# PLC-_-V3.net
KiCad netlist of a schematic drawn in Altium Designer
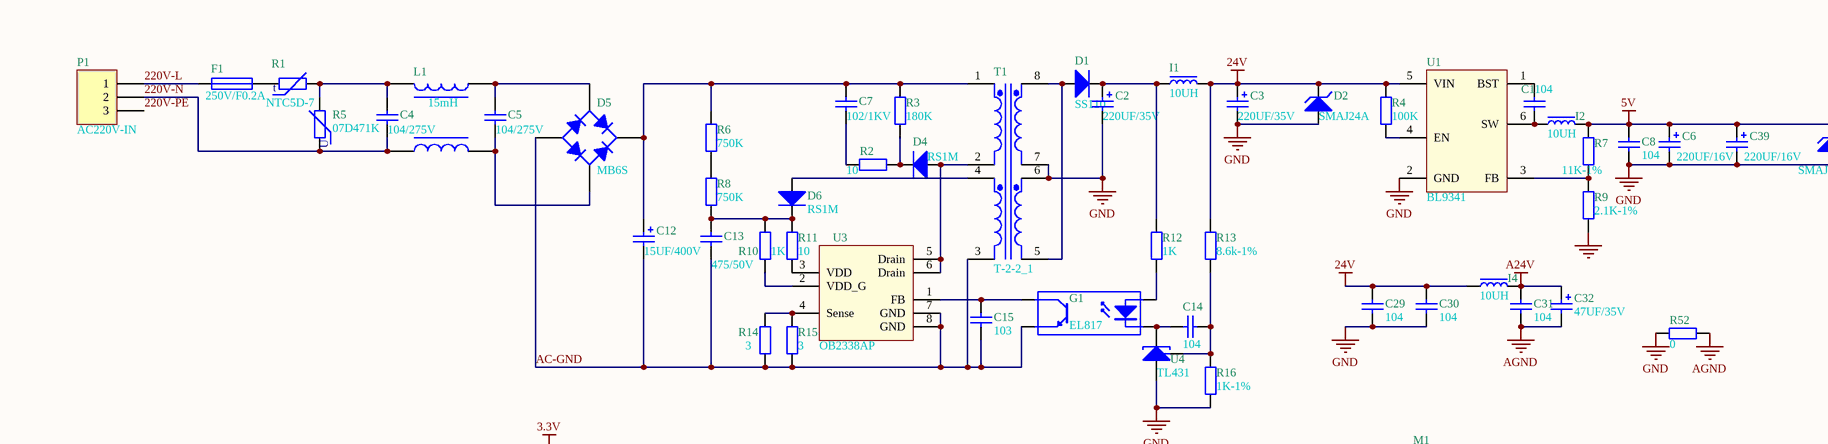
[diagram p0: PLC-无线通讯版-V3.SchDoc, top left]
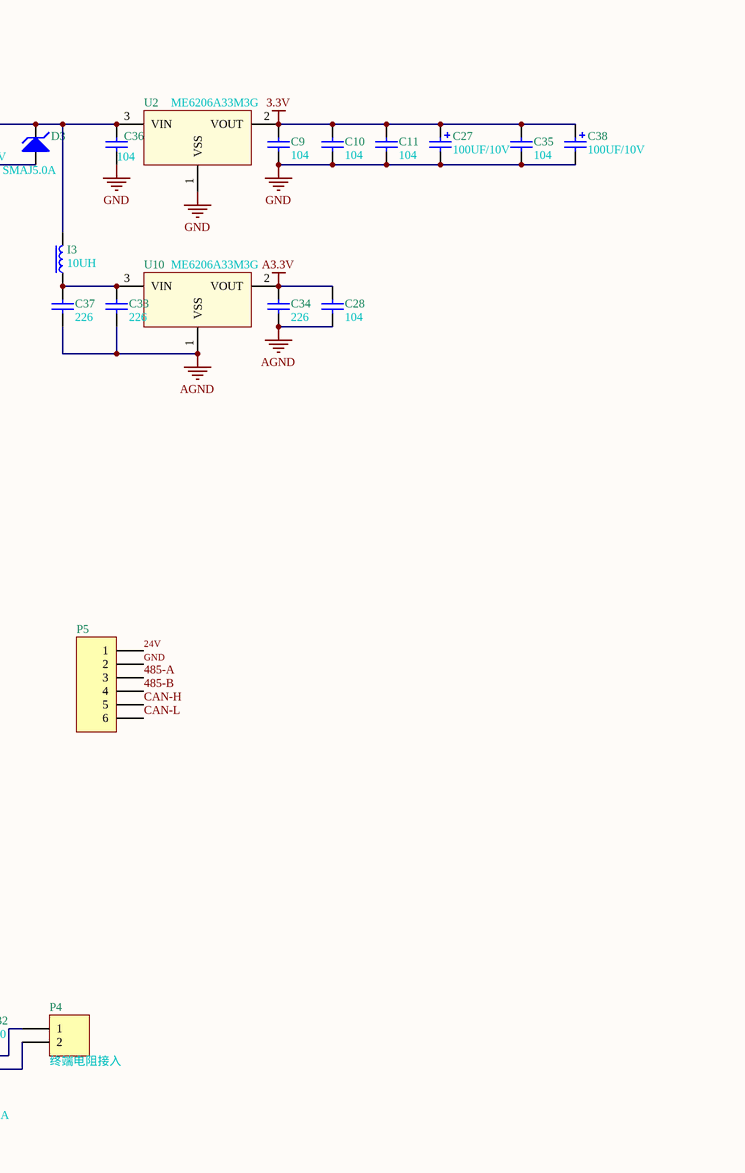
[diagram p1: PLC-无线通讯版-V3.SchDoc, top right]
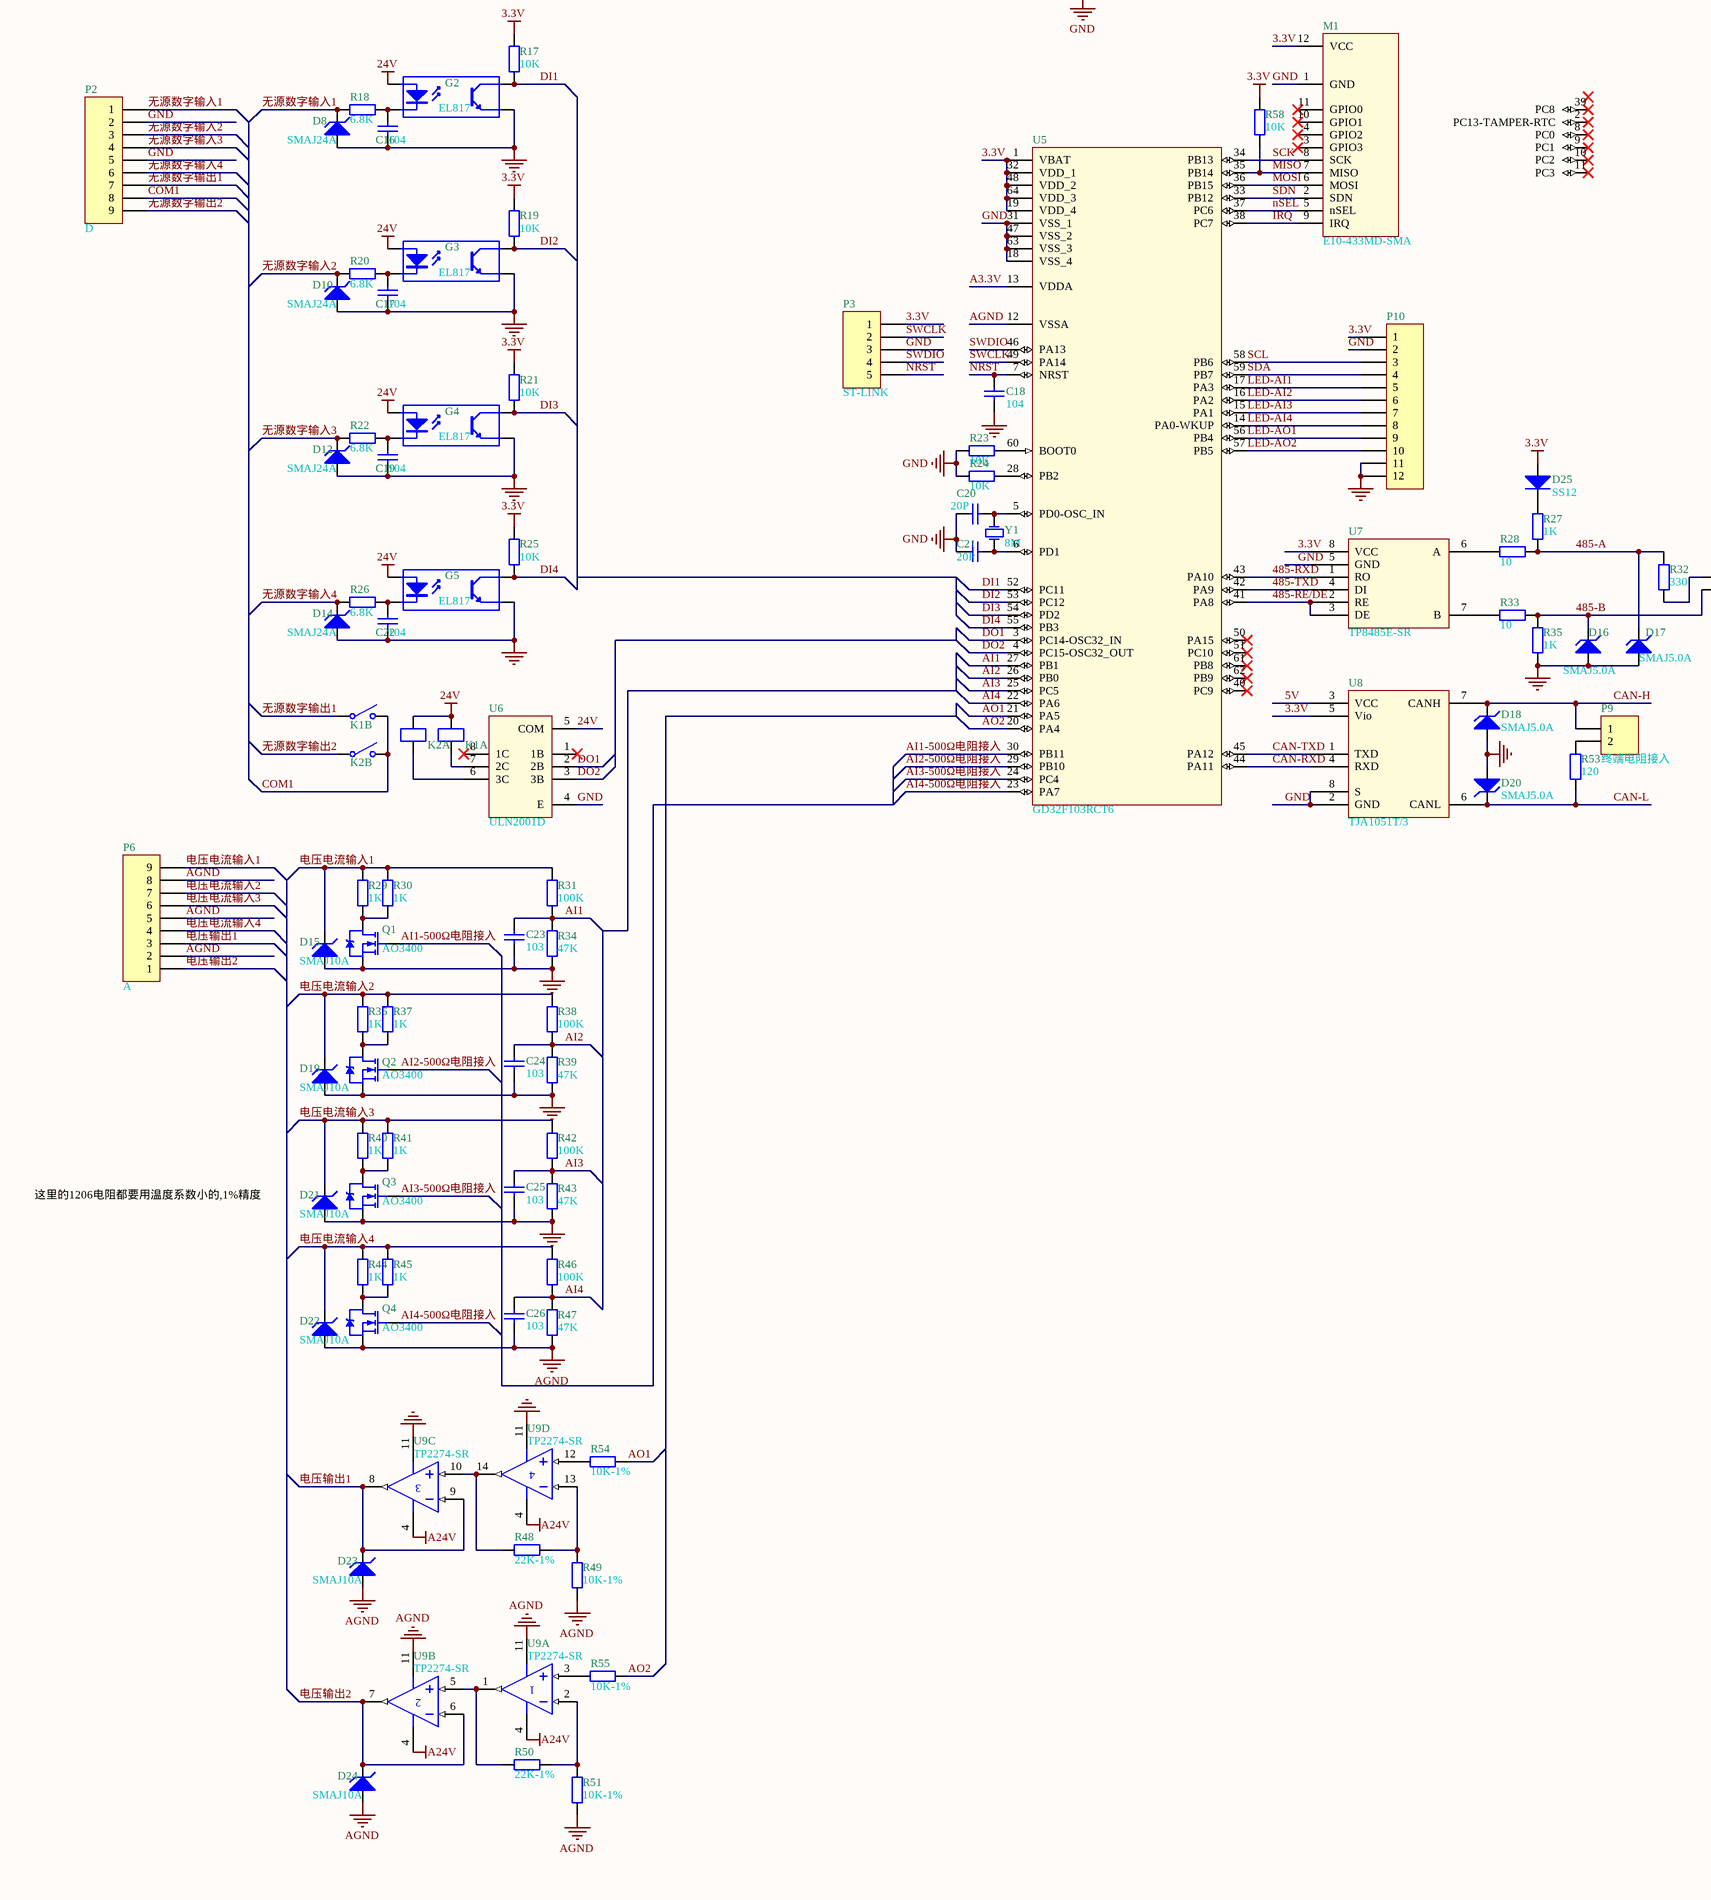
[diagram p2: PLC-无线通讯版-V3.SchDoc, bottom left]
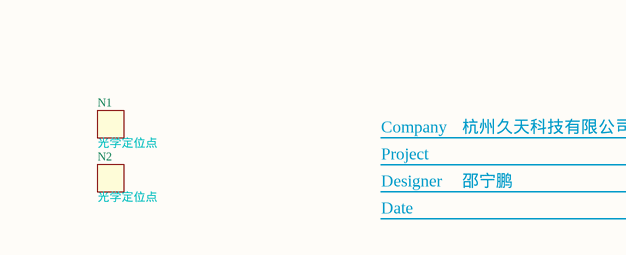
[diagram p3: PLC-无线通讯版-V3.SchDoc, bottom right]

(export (version "E")
  (design (tool "Eeschema 10.0.6"))
  (components
    (comp (ref "C1")
      (value "104")
      (footprint "C-0603")
      (description "Capacitor")
      (fields (field (name "PUBLISHER") "Altium Limited"))
      (libsource (lib "元件2.0") (part "Cap"))
    )
    (comp (ref "C2")
      (value "220UF/35V")
      (footprint "贴片固态电容8*10-M")
      (description "电解电容")
      (fields (field (name "PUBLISHER") "Altium Limited"))
      (libsource (lib "2电容-V1.0") (part "Cap Pol1"))
    )
    (comp (ref "C3")
      (value "220UF/35V")
      (footprint "贴片固态电容8*10-M")
      (description "电解电容")
      (fields (field (name "PUBLISHER") "Altium Limited"))
      (libsource (lib "2电容-V1.0") (part "Cap Pol1"))
    )
    (comp (ref "C4")
      (value "104/275V")
      (footprint "安规电容 脚距10")
      (description "Capacitor")
      (fields (field (name "PUBLISHER") "Altium Limited"))
      (libsource (lib "元件2.0") (part "Cap"))
    )
    (comp (ref "C5")
      (value "104/275V")
      (footprint "安规电容 脚距10")
      (description "Capacitor")
      (fields (field (name "PUBLISHER") "Altium Limited"))
      (libsource (lib "元件2.0") (part "Cap"))
    )
    (comp (ref "C6")
      (value "220UF/16V")
      (footprint "贴片固态电容6.3*7.7")
      (description "Polarized Capacitor (Radial)")
      (fields (field (name "PUBLISHER") "Altium Limited"))
      (libsource (lib "元件2.0") (part "Cap Pol1"))
    )
    (comp (ref "C7")
      (value "102/1KV")
      (footprint "C-1206-M")
      (description "0805")
      (fields (field (name "PUBLISHER") "Altium Limited"))
      (libsource (lib "2电容-V1.0") (part "Cap-0603"))
    )
    (comp (ref "C8")
      (value "104")
      (footprint "C-0603")
      (description "Capacitor")
      (fields (field (name "PUBLISHER") "Altium Limited"))
      (libsource (lib "元件2.0") (part "Cap"))
    )
    (comp (ref "C9")
      (value "104")
      (footprint "C-0603")
      (description "Capacitor")
      (fields (field (name "PUBLISHER") "Altium Limited"))
      (libsource (lib "元件2.0") (part "Cap"))
    )
    (comp (ref "C10")
      (value "104")
      (footprint "C-0603")
      (description "Capacitor")
      (fields (field (name "PUBLISHER") "Altium Limited"))
      (libsource (lib "元件2.0") (part "Cap"))
    )
    (comp (ref "C11")
      (value "104")
      (footprint "C-0603")
      (description "Capacitor")
      (fields (field (name "PUBLISHER") "Altium Limited"))
      (libsource (lib "元件2.0") (part "Cap"))
    )
    (comp (ref "C12")
      (value "15UF/400V")
      (footprint "电解电容10*20蓝色")
      (description "电解电容")
      (fields (field (name "PUBLISHER") "Altium Limited"))
      (libsource (lib "2电容-V1.0") (part "Cap Pol1"))
    )
    (comp (ref "C13")
      (value "475/50V")
      (footprint "C-1206-M")
      (description "Capacitor")
      (fields (field (name "PUBLISHER") "Altium Limited"))
      (libsource (lib "元件2.0") (part "Cap"))
    )
    (comp (ref "C14")
      (value "104")
      (footprint "C-0603")
      (description "Capacitor")
      (fields (field (name "PUBLISHER") "Altium Limited"))
      (libsource (lib "元件2.0") (part "Cap"))
    )
    (comp (ref "C15")
      (value "103")
      (footprint "C-0603")
      (description "Capacitor")
      (fields (field (name "PUBLISHER") "Altium Limited"))
      (libsource (lib "元件2.0") (part "Cap"))
    )
    (comp (ref "C16")
      (value "104")
      (footprint "C-0603")
      (description "0805")
      (fields (field (name "PUBLISHER") "Altium Limited"))
      (libsource (lib "2电容-V1.0") (part "Cap-0603"))
    )
    (comp (ref "C17")
      (value "104")
      (footprint "C-0603")
      (description "0805")
      (fields (field (name "PUBLISHER") "Altium Limited"))
      (libsource (lib "2电容-V1.0") (part "Cap-0603"))
    )
    (comp (ref "C18")
      (value "104")
      (footprint "C-0603")
      (description "0805")
      (fields (field (name "PUBLISHER") "Altium Limited"))
      (libsource (lib "2电容-V1.0") (part "Cap-0603"))
    )
    (comp (ref "C19")
      (value "104")
      (footprint "C-0603")
      (description "0805")
      (fields (field (name "PUBLISHER") "Altium Limited"))
      (libsource (lib "2电容-V1.0") (part "Cap-0603"))
    )
    (comp (ref "C20")
      (value "20P")
      (footprint "C-0603")
      (description "0805")
      (fields (field (name "PUBLISHER") "Altium Limited"))
      (libsource (lib "2电容-V1.0") (part "Cap-0603"))
    )
    (comp (ref "C21")
      (value "20P")
      (footprint "C-0603")
      (description "0805")
      (fields (field (name "PUBLISHER") "Altium Limited"))
      (libsource (lib "2电容-V1.0") (part "Cap-0603"))
    )
    (comp (ref "C22")
      (value "104")
      (footprint "C-0603")
      (description "0805")
      (fields (field (name "PUBLISHER") "Altium Limited"))
      (libsource (lib "2电容-V1.0") (part "Cap-0603"))
    )
    (comp (ref "C23")
      (value "103")
      (footprint "C-0603")
      (description "0805")
      (fields (field (name "PUBLISHER") "Altium Limited"))
      (libsource (lib "2电容-V1.0") (part "Cap-0603"))
    )
    (comp (ref "C24")
      (value "103")
      (footprint "C-0603")
      (description "0805")
      (fields (field (name "PUBLISHER") "Altium Limited"))
      (libsource (lib "2电容-V1.0") (part "Cap-0603"))
    )
    (comp (ref "C25")
      (value "103")
      (footprint "C-0603")
      (description "0805")
      (fields (field (name "PUBLISHER") "Altium Limited"))
      (libsource (lib "2电容-V1.0") (part "Cap-0603"))
    )
    (comp (ref "C26")
      (value "103")
      (footprint "C-0603")
      (description "0805")
      (fields (field (name "PUBLISHER") "Altium Limited"))
      (libsource (lib "2电容-V1.0") (part "Cap-0603"))
    )
    (comp (ref "C27")
      (value "100UF/10V")
      (footprint "贴片固态电容5*5.3")
      (description "Polarized Capacitor (Radial)")
      (fields (field (name "PUBLISHER") "Altium Limited"))
      (libsource (lib "元件2.0") (part "Cap Pol1"))
    )
    (comp (ref "C28")
      (value "104")
      (footprint "C-0603")
      (description "Capacitor")
      (fields (field (name "PUBLISHER") "Altium Limited"))
      (libsource (lib "元件2.0") (part "Cap"))
    )
    (comp (ref "C29")
      (value "104")
      (footprint "C-0603")
      (description "Capacitor")
      (fields (field (name "PUBLISHER") "Altium Limited"))
      (libsource (lib "元件2.0") (part "Cap"))
    )
    (comp (ref "C30")
      (value "104")
      (footprint "C-0603")
      (description "Capacitor")
      (fields (field (name "PUBLISHER") "Altium Limited"))
      (libsource (lib "元件2.0") (part "Cap"))
    )
    (comp (ref "C31")
      (value "104")
      (footprint "C-0603")
      (description "Capacitor")
      (fields (field (name "PUBLISHER") "Altium Limited"))
      (libsource (lib "元件2.0") (part "Cap"))
    )
    (comp (ref "C32")
      (value "47UF/35V")
      (footprint "贴片固态电容6.3*5.3-M")
      (description "Polarized Capacitor (Radial)")
      (fields (field (name "PUBLISHER") "Altium Limited"))
      (libsource (lib "元件2.0") (part "Cap Pol1"))
    )
    (comp (ref "C33")
      (value "226")
      (footprint "C-0805")
      (description "Capacitor")
      (fields (field (name "PUBLISHER") "Altium Limited"))
      (libsource (lib "元件2.0") (part "Cap"))
    )
    (comp (ref "C34")
      (value "226")
      (footprint "C-0805")
      (description "Capacitor")
      (fields (field (name "PUBLISHER") "Altium Limited"))
      (libsource (lib "元件2.0") (part "Cap"))
    )
    (comp (ref "C35")
      (value "104")
      (footprint "C-0603")
      (description "Capacitor")
      (fields (field (name "PUBLISHER") "Altium Limited"))
      (libsource (lib "元件2.0") (part "Cap"))
    )
    (comp (ref "C36")
      (value "104")
      (footprint "C-0603")
      (description "Capacitor")
      (fields (field (name "PUBLISHER") "Altium Limited"))
      (libsource (lib "元件2.0") (part "Cap"))
    )
    (comp (ref "C37")
      (value "226")
      (footprint "C-0805")
      (description "Capacitor")
      (fields (field (name "PUBLISHER") "Altium Limited"))
      (libsource (lib "元件2.0") (part "Cap"))
    )
    (comp (ref "C38")
      (value "100UF/10V")
      (footprint "贴片固态电容5*5.3")
      (description "Polarized Capacitor (Radial)")
      (fields (field (name "PUBLISHER") "Altium Limited"))
      (libsource (lib "元件2.0") (part "Cap Pol1"))
    )
    (comp (ref "C39")
      (value "220UF/16V")
      (footprint "贴片固态电容6.3*7.7")
      (description "Polarized Capacitor (Radial)")
      (fields (field (name "PUBLISHER") "Altium Limited"))
      (libsource (lib "元件2.0") (part "Cap Pol1"))
    )
    (comp (ref "D1")
      (value "SS110")
      (footprint "SMA")
      (description "SMA")
      (libsource (lib "4二极管-V1.1") (part "SS14"))
    )
    (comp (ref "D2")
      (value "SMAJ24A")
      (footprint "SMA")
      (description "SMB")
      (libsource (lib "4二极管-V1.1") (part "TVS-1"))
    )
    (comp (ref "D3")
      (value "SMAJ5.0A")
      (footprint "SMA")
      (description "SMB")
      (libsource (lib "4二极管-V1.1") (part "TVS-1"))
    )
    (comp (ref "D4")
      (value "RS1M")
      (footprint "SMA")
      (description "SMA")
      (libsource (lib "4二极管-V1.1") (part "SS14"))
    )
    (comp (ref "D5")
      (value "MB6S")
      (footprint "SOIC-4-MBS")
      (description "整流桥堆 MB05S-MB10S")
      (libsource (lib "4二极管-V1.1") (part "MB6S"))
    )
    (comp (ref "D6")
      (value "RS1M")
      (footprint "SMA")
      (description "SMA")
      (libsource (lib "4二极管-V1.1") (part "SS14"))
    )
    (comp (ref "D8")
      (value "SMAJ24A")
      (footprint "SMA")
      (description "SMB")
      (libsource (lib "4二极管-V1.1") (part "TVS-1"))
    )
    (comp (ref "D10")
      (value "SMAJ24A")
      (footprint "SMA")
      (description "SMB")
      (libsource (lib "4二极管-V1.1") (part "TVS-1"))
    )
    (comp (ref "D12")
      (value "SMAJ24A")
      (footprint "SMA")
      (description "SMB")
      (libsource (lib "4二极管-V1.1") (part "TVS-1"))
    )
    (comp (ref "D14")
      (value "SMAJ24A")
      (footprint "SMA")
      (description "SMB")
      (libsource (lib "4二极管-V1.1") (part "TVS-1"))
    )
    (comp (ref "D15")
      (value "SMAJ10A")
      (footprint "SMA")
      (description "SMB")
      (libsource (lib "4二极管-V1.1") (part "TVS-1"))
    )
    (comp (ref "D16")
      (value "SMAJ5.0A")
      (footprint "SMA")
      (description "SMB")
      (libsource (lib "4二极管-V1.1") (part "TVS-1"))
    )
    (comp (ref "D17")
      (value "SMAJ5.0A")
      (footprint "SMA")
      (description "SMB")
      (libsource (lib "4二极管-V1.1") (part "TVS-1"))
    )
    (comp (ref "D18")
      (value "SMAJ5.0A")
      (footprint "SMA")
      (description "SMB")
      (libsource (lib "4二极管-V1.1") (part "TVS-1"))
    )
    (comp (ref "D19")
      (value "SMAJ10A")
      (footprint "SMA")
      (description "SMB")
      (libsource (lib "4二极管-V1.1") (part "TVS-1"))
    )
    (comp (ref "D20")
      (value "SMAJ5.0A")
      (footprint "SMA")
      (description "SMB")
      (libsource (lib "4二极管-V1.1") (part "TVS-1"))
    )
    (comp (ref "D21")
      (value "SMAJ10A")
      (footprint "SMA")
      (description "SMB")
      (libsource (lib "4二极管-V1.1") (part "TVS-1"))
    )
    (comp (ref "D22")
      (value "SMAJ10A")
      (footprint "SMA")
      (description "SMB")
      (libsource (lib "4二极管-V1.1") (part "TVS-1"))
    )
    (comp (ref "D23")
      (value "SMAJ10A")
      (footprint "SMA")
      (description "SMB")
      (libsource (lib "4二极管-V1.1") (part "TVS-1"))
    )
    (comp (ref "D24")
      (value "SMAJ10A")
      (footprint "SMA")
      (description "SMB")
      (libsource (lib "4二极管-V1.1") (part "TVS-1"))
    )
    (comp (ref "D25")
      (value "SS12")
      (footprint "SMA")
      (description "SMA")
      (libsource (lib "4二极管-V1.1") (part "SS14"))
    )
    (comp (ref "F1")
      (value "250V/F0.2A")
      (footprint "FUSE-3*10带引线")
      (description "Fuse")
      (fields (field (name "PUBLISHER") "Altium Limited"))
      (libsource (lib "11其他元件-V1.0") (part "Fuse 1"))
    )
    (comp (ref "G1")
      (value "EL817")
      (footprint "SOP-4-L")
      (fields (field (name "PUBLISHER") "Altium Limited"))
      (libsource (lib "4二极管-V1.1") (part "EL817"))
    )
    (comp (ref "G2")
      (value "EL817")
      (footprint "SOP-4-L")
      (fields (field (name "PUBLISHER") "Altium Limited"))
      (libsource (lib "4二极管-V1.1") (part "EL817"))
    )
    (comp (ref "G3")
      (value "EL817")
      (footprint "SOP-4-L")
      (fields (field (name "PUBLISHER") "Altium Limited"))
      (libsource (lib "4二极管-V1.1") (part "EL817"))
    )
    (comp (ref "G4")
      (value "EL817")
      (footprint "SOP-4-L")
      (fields (field (name "PUBLISHER") "Altium Limited"))
      (libsource (lib "4二极管-V1.1") (part "EL817"))
    )
    (comp (ref "G5")
      (value "EL817")
      (footprint "SOP-4-L")
      (fields (field (name "PUBLISHER") "Altium Limited"))
      (libsource (lib "4二极管-V1.1") (part "EL817"))
    )
    (comp (ref "I1") (value "10UH") (footprint "CD43-N") (libsource (lib "3电感-V1.0") (part "Inductance3")))
    (comp (ref "I2") (value "10UH") (footprint "CD54") (libsource (lib "3电感-V1.0") (part "Inductance3")))
    (comp (ref "I3") (value "10UH") (footprint "CD43-N") (libsource (lib "3电感-V1.0") (part "Inductance3")))
    (comp (ref "I4") (value "10UH") (footprint "CD43-N") (libsource (lib "3电感-V1.0") (part "Inductance3")))
    (comp (ref "K1")
      (value "HF49FD-D24-1H11")
      (footprint "HF49FD-D24-1H11")
      (libsource (lib "10继电器-V1.0") (part "HF49FD-D24-1H11"))
    )
    (comp (ref "K2")
      (value "HF49FD-D24-1H11")
      (footprint "HF49FD-D24-1H11")
      (libsource (lib "") (part "HF49FD-D24-1H11_1"))
    )
    (comp (ref "L1") (value "15mH") (footprint "UU9.8") (libsource (lib "3电感-V1.0") (part "共模电感UU9.8")))
    (comp (ref "M1")
      (value "E10-433MD-SMA")
      (footprint "E10-433MD-SMA")
      (libsource (lib "6电路模块-V1.0") (part "E10-433MD-SMA"))
    )
    (comp (ref "N1") (value "光学定位点") (footprint "MARK-1mm-3mm") (libsource (lib "11其他元件-V1.0") (part "无引脚")))
    (comp (ref "N2") (value "光学定位点") (footprint "MARK-1mm-3mm") (libsource (lib "11其他元件-V1.0") (part "无引脚")))
    (comp (ref "P1")
      (value "AC220V-IN")
      (footprint "KF2EDGVC-5.08-3P")
      (description "Header, 3-Pin")
      (fields (field (name "PUBLISHER") "Altium Limited"))
      (libsource (lib "5排针-V1.0") (part "Header 3"))
    )
    (comp (ref "P2")
      (value "D")
      (footprint "2EMGKG-5.08-9P")
      (description "Header, 9-Pin")
      (fields (field (name "PUBLISHER") "Altium Limited"))
      (libsource (lib "5排针-V1.0") (part "Header 9"))
    )
    (comp (ref "P3")
      (value "ST-LINK")
      (footprint "5P下载口")
      (description "Header, 5-Pin")
      (fields (field (name "PUBLISHER") "Altium Limited"))
      (libsource (lib "5排针-V1.0") (part "Header 5"))
    )
    (comp (ref "P4")
      (value "终端电阻接入")
      (footprint "HDR1X2")
      (description "Header, 2-Pin")
      (fields (field (name "PUBLISHER") "Altium Limited"))
      (libsource (lib "5排针-V1.0") (part "Header 2"))
    )
    (comp (ref "P5")
      (value "~")
      (footprint "2EMGKG-5.08-6P")
      (description "Header, 6-Pin")
      (fields (field (name "PUBLISHER") "Altium Limited"))
      (libsource (lib "5排针-V1.0") (part "Header 6"))
    )
    (comp (ref "P6")
      (value "A")
      (footprint "2EMGKG-5.08-9P")
      (description "Header, 9-Pin")
      (fields (field (name "PUBLISHER") "Altium Limited"))
      (libsource (lib "") (part "Header 9_1"))
    )
    (comp (ref "P9")
      (value "终端电阻接入")
      (footprint "HDR1X2")
      (description "Header, 2-Pin")
      (fields (field (name "PUBLISHER") "Altium Limited"))
      (libsource (lib "5排针-V1.0") (part "Header 2"))
    )
    (comp (ref "P10")
      (value "~")
      (footprint "FPC-1.0MM立贴错位_10P")
      (description "Header, 12-Pin")
      (fields (field (name "PUBLISHER") "Altium Limited"))
      (libsource (lib "5排针-V1.0") (part "Header 12"))
    )
    (comp (ref "Q1")
      (value "AO3400")
      (footprint "SOT-23")
      (description "SOT-23")
      (libsource (lib "4二极管-V1.1") (part "AO3400"))
    )
    (comp (ref "Q2")
      (value "AO3400")
      (footprint "SOT-23")
      (description "SOT-23")
      (libsource (lib "4二极管-V1.1") (part "AO3400"))
    )
    (comp (ref "Q3")
      (value "AO3400")
      (footprint "SOT-23")
      (description "SOT-23")
      (libsource (lib "4二极管-V1.1") (part "AO3400"))
    )
    (comp (ref "Q4")
      (value "AO3400")
      (footprint "SOT-23")
      (description "SOT-23")
      (libsource (lib "4二极管-V1.1") (part "AO3400"))
    )
    (comp (ref "R1")
      (value "NTC5D-7")
      (footprint "NTC-5D-7")
      (fields (field (name "PUBLISHER") "Altium Limited"))
      (libsource (lib "1电阻-V1.0") (part "热敏电阻"))
    )
    (comp (ref "R2")
      (value "10")
      (footprint "R-0805")
      (description "0603")
      (fields (field (name "PUBLISHER") "Altium Limited"))
      (libsource (lib "") (part "Res2-0603_1"))
    )
    (comp (ref "R3")
      (value "180K")
      (footprint "R-1206-M")
      (description "0603")
      (fields (field (name "PUBLISHER") "Altium Limited"))
      (libsource (lib "1电阻-V1.0") (part "Res2-0603"))
    )
    (comp (ref "R4")
      (value "100K")
      (footprint "R-0603")
      (description "0603")
      (fields (field (name "PUBLISHER") "Altium Limited"))
      (libsource (lib "") (part "Res2-0603_2"))
    )
    (comp (ref "R5") (value "07D471K") (footprint "MOV-07D") (libsource (lib "1电阻-V1.0") (part "压敏电阻")))
    (comp (ref "R6")
      (value "750K")
      (footprint "R-1206-M")
      (description "1%")
      (fields (field (name "PUBLISHER") "Altium Limited"))
      (libsource (lib "") (part "Res2_1"))
    )
    (comp (ref "R7")
      (value "11K-1%")
      (footprint "R-0603")
      (description "0603")
      (fields (field (name "PUBLISHER") "Altium Limited"))
      (libsource (lib "") (part "Res2-0603_2"))
    )
    (comp (ref "R8")
      (value "750K")
      (footprint "R-1206-M")
      (description "1%")
      (fields (field (name "PUBLISHER") "Altium Limited"))
      (libsource (lib "") (part "Res2_1"))
    )
    (comp (ref "R9")
      (value "2.1K-1%")
      (footprint "R-0603")
      (description "0603")
      (fields (field (name "PUBLISHER") "Altium Limited"))
      (libsource (lib "") (part "Res2-0603_2"))
    )
    (comp (ref "R10")
      (value "1K")
      (footprint "R-0603")
      (description "0603")
      (fields (field (name "PUBLISHER") "Altium Limited"))
      (libsource (lib "1电阻-V1.0") (part "Res2-0603"))
    )
    (comp (ref "R11")
      (value "10")
      (footprint "R-0603")
      (description "0603")
      (fields (field (name "PUBLISHER") "Altium Limited"))
      (libsource (lib "1电阻-V1.0") (part "Res2-0603"))
    )
    (comp (ref "R12")
      (value "1K")
      (footprint "R-0603")
      (description "1%")
      (fields (field (name "PUBLISHER") "Altium Limited"))
      (libsource (lib "元件2.0") (part "Res2"))
    )
    (comp (ref "R13")
      (value "8.6k-1%")
      (footprint "R-0603")
      (description "1%")
      (fields (field (name "PUBLISHER") "Altium Limited"))
      (libsource (lib "元件2.0") (part "Res2"))
    )
    (comp (ref "R14")
      (value "3")
      (footprint "R-1206-M")
      (description "0603")
      (fields (field (name "PUBLISHER") "Altium Limited"))
      (libsource (lib "1电阻-V1.0") (part "Res2-0603"))
    )
    (comp (ref "R15")
      (value "3")
      (footprint "R-1206-M")
      (description "0603")
      (fields (field (name "PUBLISHER") "Altium Limited"))
      (libsource (lib "1电阻-V1.0") (part "Res2-0603"))
    )
    (comp (ref "R16")
      (value "1K-1%")
      (footprint "R-0603")
      (description "1%")
      (fields (field (name "PUBLISHER") "Altium Limited"))
      (libsource (lib "元件2.0") (part "Res2"))
    )
    (comp (ref "R17")
      (value "10K")
      (footprint "R-0603")
      (description "0603")
      (fields (field (name "PUBLISHER") "Altium Limited"))
      (libsource (lib "1电阻-V1.0") (part "Res2-0603"))
    )
    (comp (ref "R18")
      (value "6.8K")
      (footprint "R-0603")
      (description "0603")
      (fields (field (name "PUBLISHER") "Altium Limited"))
      (libsource (lib "") (part "Res2-0603_1"))
    )
    (comp (ref "R19")
      (value "10K")
      (footprint "R-0603")
      (description "0603")
      (fields (field (name "PUBLISHER") "Altium Limited"))
      (libsource (lib "1电阻-V1.0") (part "Res2-0603"))
    )
    (comp (ref "R20")
      (value "6.8K")
      (footprint "R-0603")
      (description "0603")
      (fields (field (name "PUBLISHER") "Altium Limited"))
      (libsource (lib "") (part "Res2-0603_1"))
    )
    (comp (ref "R21")
      (value "10K")
      (footprint "R-0603")
      (description "0603")
      (fields (field (name "PUBLISHER") "Altium Limited"))
      (libsource (lib "1电阻-V1.0") (part "Res2-0603"))
    )
    (comp (ref "R22")
      (value "6.8K")
      (footprint "R-0603")
      (description "0603")
      (fields (field (name "PUBLISHER") "Altium Limited"))
      (libsource (lib "") (part "Res2-0603_1"))
    )
    (comp (ref "R23")
      (value "10K")
      (footprint "R-0603")
      (description "0603")
      (fields (field (name "PUBLISHER") "Altium Limited"))
      (libsource (lib "") (part "Res2-0603_2"))
    )
    (comp (ref "R24")
      (value "10K")
      (footprint "R-0603")
      (description "0603")
      (fields (field (name "PUBLISHER") "Altium Limited"))
      (libsource (lib "") (part "Res2-0603_2"))
    )
    (comp (ref "R25")
      (value "10K")
      (footprint "R-0603")
      (description "0603")
      (fields (field (name "PUBLISHER") "Altium Limited"))
      (libsource (lib "1电阻-V1.0") (part "Res2-0603"))
    )
    (comp (ref "R26")
      (value "6.8K")
      (footprint "R-0603")
      (description "0603")
      (fields (field (name "PUBLISHER") "Altium Limited"))
      (libsource (lib "") (part "Res2-0603_1"))
    )
    (comp (ref "R27")
      (value "1K")
      (footprint "R-0603")
      (description "Resistor")
      (fields (field (name "PUBLISHER") "Altium Limited"))
      (libsource (lib "") (part "Res2_2"))
    )
    (comp (ref "R28")
      (value "10")
      (footprint "R-0805-M")
      (description "Resistor")
      (fields (field (name "PUBLISHER") "Altium Limited"))
      (libsource (lib "Miscellaneous Devices") (part "Res2"))
    )
    (comp (ref "R29")
      (value "1K")
      (footprint "R-1206-M")
      (description "0603")
      (fields (field (name "PUBLISHER") "Altium Limited"))
      (libsource (lib "1电阻-V1.0") (part "Res2-0603"))
    )
    (comp (ref "R30")
      (value "1K")
      (footprint "R-1206-M")
      (description "0603")
      (fields (field (name "PUBLISHER") "Altium Limited"))
      (libsource (lib "1电阻-V1.0") (part "Res2-0603"))
    )
    (comp (ref "R31")
      (value "100K")
      (footprint "R-1206-M")
      (description "0603")
      (fields (field (name "PUBLISHER") "Altium Limited"))
      (libsource (lib "1电阻-V1.0") (part "Res2-0603"))
    )
    (comp (ref "R32")
      (value "330")
      (footprint "R-1206-M")
      (description "Resistor")
      (fields (field (name "PUBLISHER") "Altium Limited"))
      (libsource (lib "") (part "Res2_1"))
    )
    (comp (ref "R33")
      (value "10")
      (footprint "R-0805-M")
      (description "Resistor")
      (fields (field (name "PUBLISHER") "Altium Limited"))
      (libsource (lib "Miscellaneous Devices") (part "Res2"))
    )
    (comp (ref "R34")
      (value "47K")
      (footprint "R-1206-M")
      (description "0603")
      (fields (field (name "PUBLISHER") "Altium Limited"))
      (libsource (lib "1电阻-V1.0") (part "Res2-0603"))
    )
    (comp (ref "R35")
      (value "1K")
      (footprint "R-0603")
      (description "Resistor")
      (fields (field (name "PUBLISHER") "Altium Limited"))
      (libsource (lib "") (part "Res2_3"))
    )
    (comp (ref "R36")
      (value "1K")
      (footprint "R-1206-M")
      (description "0603")
      (fields (field (name "PUBLISHER") "Altium Limited"))
      (libsource (lib "1电阻-V1.0") (part "Res2-0603"))
    )
    (comp (ref "R37")
      (value "1K")
      (footprint "R-1206-M")
      (description "0603")
      (fields (field (name "PUBLISHER") "Altium Limited"))
      (libsource (lib "1电阻-V1.0") (part "Res2-0603"))
    )
    (comp (ref "R38")
      (value "100K")
      (footprint "R-1206-M")
      (description "0603")
      (fields (field (name "PUBLISHER") "Altium Limited"))
      (libsource (lib "1电阻-V1.0") (part "Res2-0603"))
    )
    (comp (ref "R39")
      (value "47K")
      (footprint "R-1206-M")
      (description "0603")
      (fields (field (name "PUBLISHER") "Altium Limited"))
      (libsource (lib "1电阻-V1.0") (part "Res2-0603"))
    )
    (comp (ref "R40")
      (value "1K")
      (footprint "R-1206-M")
      (description "0603")
      (fields (field (name "PUBLISHER") "Altium Limited"))
      (libsource (lib "1电阻-V1.0") (part "Res2-0603"))
    )
    (comp (ref "R41")
      (value "1K")
      (footprint "R-1206-M")
      (description "0603")
      (fields (field (name "PUBLISHER") "Altium Limited"))
      (libsource (lib "1电阻-V1.0") (part "Res2-0603"))
    )
    (comp (ref "R42")
      (value "100K")
      (footprint "R-1206-M")
      (description "0603")
      (fields (field (name "PUBLISHER") "Altium Limited"))
      (libsource (lib "1电阻-V1.0") (part "Res2-0603"))
    )
    (comp (ref "R43")
      (value "47K")
      (footprint "R-1206-M")
      (description "0603")
      (fields (field (name "PUBLISHER") "Altium Limited"))
      (libsource (lib "1电阻-V1.0") (part "Res2-0603"))
    )
    (comp (ref "R44")
      (value "1K")
      (footprint "R-1206-M")
      (description "0603")
      (fields (field (name "PUBLISHER") "Altium Limited"))
      (libsource (lib "1电阻-V1.0") (part "Res2-0603"))
    )
    (comp (ref "R45")
      (value "1K")
      (footprint "R-1206-M")
      (description "0603")
      (fields (field (name "PUBLISHER") "Altium Limited"))
      (libsource (lib "1电阻-V1.0") (part "Res2-0603"))
    )
    (comp (ref "R46")
      (value "100K")
      (footprint "R-1206-M")
      (description "0603")
      (fields (field (name "PUBLISHER") "Altium Limited"))
      (libsource (lib "1电阻-V1.0") (part "Res2-0603"))
    )
    (comp (ref "R47")
      (value "47K")
      (footprint "R-1206-M")
      (description "0603")
      (fields (field (name "PUBLISHER") "Altium Limited"))
      (libsource (lib "1电阻-V1.0") (part "Res2-0603"))
    )
    (comp (ref "R48")
      (value "22K-1%")
      (footprint "R-0603")
      (description "0603")
      (fields (field (name "PUBLISHER") "Altium Limited"))
      (libsource (lib "") (part "Res2-0603_2"))
    )
    (comp (ref "R49")
      (value "10K-1%")
      (footprint "R-0603")
      (description "0603")
      (fields (field (name "PUBLISHER") "Altium Limited"))
      (libsource (lib "") (part "Res2-0603_3"))
    )
    (comp (ref "R50")
      (value "22K-1%")
      (footprint "R-0603")
      (description "0603")
      (fields (field (name "PUBLISHER") "Altium Limited"))
      (libsource (lib "") (part "Res2-0603_2"))
    )
    (comp (ref "R51")
      (value "10K-1%")
      (footprint "R-0603")
      (description "0603")
      (fields (field (name "PUBLISHER") "Altium Limited"))
      (libsource (lib "") (part "Res2-0603_3"))
    )
    (comp (ref "R52")
      (value "0")
      (footprint "R-0603")
      (description "0603")
      (fields (field (name "PUBLISHER") "Altium Limited"))
      (libsource (lib "1电阻-V1.0") (part "Res2-0603"))
    )
    (comp (ref "R53")
      (value "120")
      (footprint "R-1206")
      (description "Resistor")
      (fields (field (name "PUBLISHER") "Altium Limited"))
      (libsource (lib "") (part "Res2_1"))
    )
    (comp (ref "R54")
      (value "10K-1%")
      (footprint "R-0603")
      (description "0603")
      (fields (field (name "PUBLISHER") "Altium Limited"))
      (libsource (lib "") (part "Res2-0603_1"))
    )
    (comp (ref "R55")
      (value "10K-1%")
      (footprint "R-0603")
      (description "0603")
      (fields (field (name "PUBLISHER") "Altium Limited"))
      (libsource (lib "") (part "Res2-0603_1"))
    )
    (comp (ref "R58")
      (value "10K")
      (footprint "R-0603")
      (description "0603")
      (fields (field (name "PUBLISHER") "Altium Limited"))
      (libsource (lib "1电阻-V1.0") (part "Res2-0603"))
    )
    (comp (ref "T1") (value "T-2-2_1") (footprint "EE19-卧式") (libsource (lib "3电感-V1.0") (part "T-2-2_1")))
    (comp (ref "U1") (value "BL9341") (footprint "SOT-23-6-N") (libsource (lib "电源芯片DC-DC") (part "BL9341")))
    (comp (ref "U2")
      (value "ME6206A33M3G")
      (footprint "SOT-23")
      (description "LDO稳压 SOT-23")
      (libsource (lib "电源芯片-线性稳压-V1") (part "ME6206A33M3G"))
    )
    (comp (ref "U3") (value "OB2338AP") (footprint "DIP8") (libsource (lib "AC-DC控制芯片") (part "OB2338AP")))
    (comp (ref "U4")
      (value "TL431")
      (footprint "SOT-23")
      (description "稳压芯片 SOT-23")
      (libsource (lib "电源芯片-线性稳压-V1") (part "TL431"))
    )
    (comp (ref "U5")
      (value "GD32F103RCT6")
      (footprint "LQFP64-M")
      (libsource (lib "9单片机-V1.0") (part "STM32F103RBT6"))
    )
    (comp (ref "U6")
      (value "ULN2001D")
      (footprint "SOP-8-N")
      (libsource (lib "8集成电路-V1.1") (part "ULN2001D"))
    )
    (comp (ref "U7")
      (value "TP8485E-SR")
      (footprint "SOP-8-N")
      (description "RS485总线转串口")
      (libsource (lib "集成电路1.0") (part "MAX3082"))
    )
    (comp (ref "U8") (value "TJA1051T/3") (footprint "SOP-8-N") (libsource (lib "通讯-V1") (part "TJA1051T/3")))
    (comp (ref "U9")
      (value "TP2274-SR")
      (footprint "SOP-14-M")
      (description "四运放-SOP-14")
      (libsource (lib "8集成电路-V1.1") (part "MCP6004"))
    )
    (comp (ref "U10")
      (value "ME6206A33M3G")
      (footprint "SOT-23")
      (description "LDO稳压 SOT-23")
      (libsource (lib "电源芯片-线性稳压-V1") (part "ME6206A33M3G"))
    )
    (comp (ref "Y1") (value "8M") (footprint "HC-49SMD") (libsource (lib "11其他元件-V1.0") (part "晶振")))
  )
  (nets
    (net (code "1") (name "/220V-L") (class "Default")
      (node (ref "F1") (pin "1") (pinfunction "1_1") (pintype "passive"))
      (node (ref "P1") (pin "1") (pinfunction "1_1") (pintype "passive"))
    )
    (net (code "2") (name "/220V-N") (class "Default")
      (node (ref "C4") (pin "2") (pinfunction "2_2") (pintype "passive"))
      (node (ref "L1") (pin "1") (pinfunction "1_1") (pintype "passive"))
      (node (ref "P1") (pin "2") (pinfunction "2_2") (pintype "passive"))
      (node (ref "R5") (pin "1") (pinfunction "1_1") (pintype "passive"))
    )
    (net (code "3") (name "/220V-PE") (class "Default")
      (node (ref "P1") (pin "3") (pinfunction "3_3") (pintype "passive"))
    )
    (net (code "4") (name "/485-A") (class "Default")
      (node (ref "D17") (pin "2") (pinfunction "K_2") (pintype "passive"))
      (node (ref "P5") (pin "3") (pinfunction "3_3") (pintype "passive"))
      (node (ref "R27") (pin "2") (pinfunction "2_2") (pintype "passive"))
      (node (ref "R28") (pin "1") (pinfunction "1_1") (pintype "passive"))
      (node (ref "R32") (pin "1") (pinfunction "1_1") (pintype "passive"))
    )
    (net (code "5") (name "/485-B") (class "Default")
      (node (ref "D16") (pin "2") (pinfunction "K_2") (pintype "passive"))
      (node (ref "P4") (pin "2") (pinfunction "2_2") (pintype "passive"))
      (node (ref "P5") (pin "4") (pinfunction "4_4") (pintype "passive"))
      (node (ref "R33") (pin "1") (pinfunction "1_1") (pintype "passive"))
      (node (ref "R35") (pin "2") (pinfunction "2_2") (pintype "passive"))
    )
    (net (code "6") (name "/485-RE{slash}DE") (class "Default")
      (node (ref "U5") (pin "41") (pinfunction "PA8_41") (pintype "bidirectional"))
      (node (ref "U7") (pin "2") (pinfunction "RE_2") (pintype "passive"))
      (node (ref "U7") (pin "3") (pinfunction "DE_3") (pintype "passive"))
    )
    (net (code "7") (name "/485-RXD") (class "Default")
      (node (ref "U5") (pin "43") (pinfunction "PA10_43") (pintype "bidirectional"))
      (node (ref "U7") (pin "1") (pinfunction "RO_1") (pintype "passive"))
    )
    (net (code "8") (name "/485-TXD") (class "Default")
      (node (ref "U5") (pin "42") (pinfunction "PA9_42") (pintype "bidirectional"))
      (node (ref "U7") (pin "4") (pinfunction "DI_4") (pintype "passive"))
    )
    (net (code "9") (name "/AC-GND") (class "Default")
      (node (ref "C12") (pin "2") (pinfunction "2_2") (pintype "passive"))
      (node (ref "C13") (pin "1") (pinfunction "1_1") (pintype "passive"))
      (node (ref "C15") (pin "1") (pinfunction "1_1") (pintype "passive"))
      (node (ref "D5") (pin "4") (pinfunction "A_4") (pintype "passive"))
      (node (ref "G1") (pin "3") (pinfunction "E_3") (pintype "passive"))
      (node (ref "R14") (pin "1") (pinfunction "1_1") (pintype "passive"))
      (node (ref "R15") (pin "1") (pinfunction "1_1") (pintype "passive"))
      (node (ref "T1") (pin "3") (pinfunction "3_3") (pintype "passive"))
      (node (ref "U3") (pin "7") (pinfunction "GND_7") (pintype "passive"))
      (node (ref "U3") (pin "8") (pinfunction "GND_8") (pintype "passive"))
    )
    (net (code "10") (name "/AI1") (class "Default")
      (node (ref "C23") (pin "2") (pinfunction "2_2") (pintype "passive"))
      (node (ref "R31") (pin "1") (pinfunction "1_1") (pintype "passive"))
      (node (ref "R34") (pin "2") (pinfunction "2_2") (pintype "passive"))
      (node (ref "U5") (pin "27") (pinfunction "PB1_27") (pintype "bidirectional"))
    )
    (net (code "11") (name "/AI1-500Ω电阻接入") (class "Default")
      (node (ref "Q1") (pin "1") (pinfunction "G_1") (pintype "passive"))
      (node (ref "U5") (pin "30") (pinfunction "PB11_30") (pintype "bidirectional"))
    )
    (net (code "12") (name "/AI2") (class "Default")
      (node (ref "C24") (pin "2") (pinfunction "2_2") (pintype "passive"))
      (node (ref "R38") (pin "1") (pinfunction "1_1") (pintype "passive"))
      (node (ref "R39") (pin "2") (pinfunction "2_2") (pintype "passive"))
      (node (ref "U5") (pin "26") (pinfunction "PB0_26") (pintype "bidirectional"))
    )
    (net (code "13") (name "/AI2-500Ω电阻接入") (class "Default")
      (node (ref "Q2") (pin "1") (pinfunction "G_1") (pintype "passive"))
      (node (ref "U5") (pin "29") (pinfunction "PB10_29") (pintype "bidirectional"))
    )
    (net (code "14") (name "/AI3") (class "Default")
      (node (ref "C25") (pin "2") (pinfunction "2_2") (pintype "passive"))
      (node (ref "R42") (pin "1") (pinfunction "1_1") (pintype "passive"))
      (node (ref "R43") (pin "2") (pinfunction "2_2") (pintype "passive"))
      (node (ref "U5") (pin "25") (pinfunction "PC5_25") (pintype "bidirectional"))
    )
    (net (code "15") (name "/AI3-500Ω电阻接入") (class "Default")
      (node (ref "Q3") (pin "1") (pinfunction "G_1") (pintype "passive"))
      (node (ref "U5") (pin "24") (pinfunction "PC4_24") (pintype "bidirectional"))
    )
    (net (code "16") (name "/AI4") (class "Default")
      (node (ref "C26") (pin "2") (pinfunction "2_2") (pintype "passive"))
      (node (ref "R46") (pin "1") (pinfunction "1_1") (pintype "passive"))
      (node (ref "R47") (pin "2") (pinfunction "2_2") (pintype "passive"))
      (node (ref "U5") (pin "22") (pinfunction "PA6_22") (pintype "bidirectional"))
    )
    (net (code "17") (name "/AI4-500Ω电阻接入") (class "Default")
      (node (ref "Q4") (pin "1") (pinfunction "G_1") (pintype "passive"))
      (node (ref "U5") (pin "23") (pinfunction "PA7_23") (pintype "bidirectional"))
    )
    (net (code "18") (name "/AO1") (class "Default")
      (node (ref "R54") (pin "2") (pinfunction "2_2") (pintype "passive"))
      (node (ref "U5") (pin "21") (pinfunction "PA5_21") (pintype "bidirectional"))
    )
    (net (code "19") (name "/AO2") (class "Default")
      (node (ref "R55") (pin "2") (pinfunction "2_2") (pintype "passive"))
      (node (ref "U5") (pin "20") (pinfunction "PA4_20") (pintype "bidirectional"))
    )
    (net (code "20") (name "/CAN-H") (class "Default")
      (node (ref "D18") (pin "2") (pinfunction "K_2") (pintype "passive"))
      (node (ref "P5") (pin "5") (pinfunction "5_5") (pintype "passive"))
      (node (ref "P9") (pin "1") (pinfunction "1_1") (pintype "passive"))
      (node (ref "U8") (pin "7") (pinfunction "CANH_7") (pintype "passive"))
    )
    (net (code "21") (name "/CAN-L") (class "Default")
      (node (ref "D20") (pin "2") (pinfunction "K_2") (pintype "passive"))
      (node (ref "P5") (pin "6") (pinfunction "6_6") (pintype "passive"))
      (node (ref "R53") (pin "2") (pinfunction "2_2") (pintype "passive"))
      (node (ref "U8") (pin "6") (pinfunction "CANL_6") (pintype "passive"))
    )
    (net (code "22") (name "/CAN-RXD") (class "Default")
      (node (ref "U5") (pin "44") (pinfunction "PA11_44") (pintype "bidirectional"))
      (node (ref "U8") (pin "4") (pinfunction "RXD_4") (pintype "passive"))
    )
    (net (code "23") (name "/CAN-TXD") (class "Default")
      (node (ref "U5") (pin "45") (pinfunction "PA12_45") (pintype "bidirectional"))
      (node (ref "U8") (pin "1") (pinfunction "TXD_1") (pintype "passive"))
    )
    (net (code "24") (name "/COM1") (class "Default")
      (node (ref "K1") (pin "4") (pinfunction "4_4") (pintype "passive"))
      (node (ref "K2") (pin "4") (pinfunction "4_4") (pintype "passive"))
      (node (ref "P2") (pin "8") (pinfunction "8_8") (pintype "passive"))
    )
    (net (code "25") (name "/DI1") (class "Default")
      (node (ref "G2") (pin "4") (pinfunction "C_4") (pintype "passive"))
      (node (ref "R17") (pin "1") (pinfunction "1_1") (pintype "passive"))
      (node (ref "U5") (pin "52") (pinfunction "PC11_52") (pintype "bidirectional"))
    )
    (net (code "26") (name "/DI2") (class "Default")
      (node (ref "G3") (pin "4") (pinfunction "C_4") (pintype "passive"))
      (node (ref "R19") (pin "1") (pinfunction "1_1") (pintype "passive"))
      (node (ref "U5") (pin "53") (pinfunction "PC12_53") (pintype "bidirectional"))
    )
    (net (code "27") (name "/DI3") (class "Default")
      (node (ref "G4") (pin "4") (pinfunction "C_4") (pintype "passive"))
      (node (ref "R21") (pin "1") (pinfunction "1_1") (pintype "passive"))
      (node (ref "U5") (pin "54") (pinfunction "PD2_54") (pintype "bidirectional"))
    )
    (net (code "28") (name "/DI4") (class "Default")
      (node (ref "G5") (pin "4") (pinfunction "C_4") (pintype "passive"))
      (node (ref "R25") (pin "1") (pinfunction "1_1") (pintype "passive"))
      (node (ref "U5") (pin "55") (pinfunction "PB3_55") (pintype "bidirectional"))
    )
    (net (code "29") (name "/DO1") (class "Default")
      (node (ref "U5") (pin "3") (pinfunction "PC14-OSC32_IN_3") (pintype "bidirectional"))
      (node (ref "U6") (pin "2") (pinfunction "2B_2") (pintype "passive"))
    )
    (net (code "30") (name "/DO2") (class "Default")
      (node (ref "U5") (pin "4") (pinfunction "PC15-OSC32_OUT_4") (pintype "bidirectional"))
      (node (ref "U6") (pin "3") (pinfunction "3B_3") (pintype "passive"))
    )
    (net (code "31") (name "/IRQ") (class "Default")
      (node (ref "M1") (pin "9") (pinfunction "IRQ_9") (pintype "passive"))
      (node (ref "U5") (pin "38") (pinfunction "PC7_38") (pintype "bidirectional"))
    )
    (net (code "32") (name "/LED-AI1") (class "Default")
      (node (ref "P10") (pin "5") (pinfunction "5_5") (pintype "passive"))
      (node (ref "U5") (pin "17") (pinfunction "PA3_17") (pintype "bidirectional"))
    )
    (net (code "33") (name "/LED-AI2") (class "Default")
      (node (ref "P10") (pin "6") (pinfunction "6_6") (pintype "passive"))
      (node (ref "U5") (pin "16") (pinfunction "PA2_16") (pintype "bidirectional"))
    )
    (net (code "34") (name "/LED-AI3") (class "Default")
      (node (ref "P10") (pin "7") (pinfunction "7_7") (pintype "passive"))
      (node (ref "U5") (pin "15") (pinfunction "PA1_15") (pintype "bidirectional"))
    )
    (net (code "35") (name "/LED-AI4") (class "Default")
      (node (ref "P10") (pin "8") (pinfunction "8_8") (pintype "passive"))
      (node (ref "U5") (pin "14") (pinfunction "PA0-WKUP_14") (pintype "bidirectional"))
    )
    (net (code "36") (name "/LED-AO1") (class "Default")
      (node (ref "P10") (pin "9") (pinfunction "9_9") (pintype "passive"))
      (node (ref "U5") (pin "56") (pinfunction "PB4_56") (pintype "bidirectional"))
    )
    (net (code "37") (name "/LED-AO2") (class "Default")
      (node (ref "P10") (pin "10") (pinfunction "10_10") (pintype "passive"))
      (node (ref "U5") (pin "57") (pinfunction "PB5_57") (pintype "bidirectional"))
    )
    (net (code "38") (name "/MISO") (class "Default")
      (node (ref "M1") (pin "7") (pinfunction "MISO_7") (pintype "passive"))
      (node (ref "R58") (pin "1") (pinfunction "1_1") (pintype "passive"))
      (node (ref "U5") (pin "35") (pinfunction "PB14_35") (pintype "bidirectional"))
    )
    (net (code "39") (name "/MOSI") (class "Default")
      (node (ref "M1") (pin "6") (pinfunction "MOSI_6") (pintype "passive"))
      (node (ref "U5") (pin "36") (pinfunction "PB15_36") (pintype "bidirectional"))
    )
    (net (code "40") (name "/NRST") (class "Default")
      (node (ref "C18") (pin "2") (pinfunction "2_2") (pintype "passive"))
      (node (ref "P3") (pin "5") (pinfunction "5_5") (pintype "passive"))
      (node (ref "U5") (pin "7") (pinfunction "NRST_7") (pintype "bidirectional"))
    )
    (net (code "41") (name "/SCK") (class "Default")
      (node (ref "M1") (pin "8") (pinfunction "SCK_8") (pintype "passive"))
      (node (ref "U5") (pin "34") (pinfunction "PB13_34") (pintype "bidirectional"))
    )
    (net (code "42") (name "/SCL") (class "Default")
      (node (ref "P10") (pin "3") (pinfunction "3_3") (pintype "passive"))
      (node (ref "U5") (pin "58") (pinfunction "PB6_58") (pintype "bidirectional"))
    )
    (net (code "43") (name "/SDA") (class "Default")
      (node (ref "P10") (pin "4") (pinfunction "4_4") (pintype "passive"))
      (node (ref "U5") (pin "59") (pinfunction "PB7_59") (pintype "bidirectional"))
    )
    (net (code "44") (name "/SDN") (class "Default")
      (node (ref "M1") (pin "2") (pinfunction "SDN_2") (pintype "passive"))
      (node (ref "U5") (pin "33") (pinfunction "PB12_33") (pintype "bidirectional"))
    )
    (net (code "45") (name "/SWCLK") (class "Default")
      (node (ref "P3") (pin "2") (pinfunction "2_2") (pintype "passive"))
      (node (ref "U5") (pin "49") (pinfunction "PA14_49") (pintype "bidirectional"))
    )
    (net (code "46") (name "/SWDIO") (class "Default")
      (node (ref "P3") (pin "4") (pinfunction "4_4") (pintype "passive"))
      (node (ref "U5") (pin "46") (pinfunction "PA13_46") (pintype "bidirectional"))
    )
    (net (code "47") (name "/nSEL") (class "Default")
      (node (ref "M1") (pin "5") (pinfunction "nSEL_5") (pintype "passive"))
      (node (ref "U5") (pin "37") (pinfunction "PC6_37") (pintype "bidirectional"))
    )
    (net (code "48") (name "/无源数字输入1") (class "Default")
      (node (ref "D8") (pin "2") (pinfunction "K_2") (pintype "passive"))
      (node (ref "P2") (pin "1") (pinfunction "1_1") (pintype "passive"))
      (node (ref "R18") (pin "1") (pinfunction "1_1") (pintype "passive"))
    )
    (net (code "49") (name "/无源数字输入2") (class "Default")
      (node (ref "D10") (pin "2") (pinfunction "K_2") (pintype "passive"))
      (node (ref "P2") (pin "3") (pinfunction "3_3") (pintype "passive"))
      (node (ref "R20") (pin "1") (pinfunction "1_1") (pintype "passive"))
    )
    (net (code "50") (name "/无源数字输入3") (class "Default")
      (node (ref "D12") (pin "2") (pinfunction "K_2") (pintype "passive"))
      (node (ref "P2") (pin "4") (pinfunction "4_4") (pintype "passive"))
      (node (ref "R22") (pin "1") (pinfunction "1_1") (pintype "passive"))
    )
    (net (code "51") (name "/无源数字输入4") (class "Default")
      (node (ref "D14") (pin "2") (pinfunction "K_2") (pintype "passive"))
      (node (ref "P2") (pin "6") (pinfunction "6_6") (pintype "passive"))
      (node (ref "R26") (pin "1") (pinfunction "1_1") (pintype "passive"))
    )
    (net (code "52") (name "/无源数字输出1") (class "Default")
      (node (ref "K1") (pin "3") (pinfunction "3_3") (pintype "passive"))
      (node (ref "P2") (pin "7") (pinfunction "7_7") (pintype "passive"))
    )
    (net (code "53") (name "/无源数字输出2") (class "Default")
      (node (ref "K2") (pin "3") (pinfunction "3_3") (pintype "passive"))
      (node (ref "P2") (pin "9") (pinfunction "9_9") (pintype "passive"))
    )
    (net (code "54") (name "/电压电流输入1") (class "Default")
      (node (ref "D15") (pin "2") (pinfunction "K_2") (pintype "passive"))
      (node (ref "P6") (pin "9") (pinfunction "9_9") (pintype "passive"))
      (node (ref "R29") (pin "2") (pinfunction "2_2") (pintype "passive"))
      (node (ref "R30") (pin "2") (pinfunction "2_2") (pintype "passive"))
      (node (ref "R31") (pin "2") (pinfunction "2_2") (pintype "passive"))
    )
    (net (code "55") (name "/电压电流输入2") (class "Default")
      (node (ref "D19") (pin "2") (pinfunction "K_2") (pintype "passive"))
      (node (ref "P6") (pin "7") (pinfunction "7_7") (pintype "passive"))
      (node (ref "R36") (pin "2") (pinfunction "2_2") (pintype "passive"))
      (node (ref "R37") (pin "2") (pinfunction "2_2") (pintype "passive"))
      (node (ref "R38") (pin "2") (pinfunction "2_2") (pintype "passive"))
    )
    (net (code "56") (name "/电压电流输入3") (class "Default")
      (node (ref "D21") (pin "2") (pinfunction "K_2") (pintype "passive"))
      (node (ref "P6") (pin "6") (pinfunction "6_6") (pintype "passive"))
      (node (ref "R40") (pin "2") (pinfunction "2_2") (pintype "passive"))
      (node (ref "R41") (pin "2") (pinfunction "2_2") (pintype "passive"))
      (node (ref "R42") (pin "2") (pinfunction "2_2") (pintype "passive"))
    )
    (net (code "57") (name "/电压电流输入4") (class "Default")
      (node (ref "D22") (pin "2") (pinfunction "K_2") (pintype "passive"))
      (node (ref "P6") (pin "4") (pinfunction "4_4") (pintype "passive"))
      (node (ref "R44") (pin "2") (pinfunction "2_2") (pintype "passive"))
      (node (ref "R45") (pin "2") (pinfunction "2_2") (pintype "passive"))
      (node (ref "R46") (pin "2") (pinfunction "2_2") (pintype "passive"))
    )
    (net (code "58") (name "/电压输出1") (class "Default")
      (node (ref "D23") (pin "2") (pinfunction "K_2") (pintype "passive"))
      (node (ref "P6") (pin "3") (pinfunction "3_3") (pintype "passive"))
      (node (ref "U9") (pin "8") (pinfunction "OUT_8") (pintype "output"))
      (node (ref "U9") (pin "9") (pinfunction "IN-_9") (pintype "input"))
    )
    (net (code "59") (name "/电压输出2") (class "Default")
      (node (ref "D24") (pin "2") (pinfunction "K_2") (pintype "passive"))
      (node (ref "P6") (pin "1") (pinfunction "1_1") (pintype "passive"))
      (node (ref "U9") (pin "6") (pinfunction "IN-_6") (pintype "input"))
      (node (ref "U9") (pin "7") (pinfunction "OUT_7") (pintype "output"))
    )
    (net (code "60") (name "3.3V") (class "Default")
      (node (ref "C10") (pin "2") (pinfunction "2_2") (pintype "passive"))
      (node (ref "C11") (pin "2") (pinfunction "2_2") (pintype "passive"))
      (node (ref "C27") (pin "1") (pinfunction "1_1") (pintype "passive"))
      (node (ref "C35") (pin "2") (pinfunction "2_2") (pintype "passive"))
      (node (ref "C38") (pin "1") (pinfunction "1_1") (pintype "passive"))
      (node (ref "C9") (pin "2") (pinfunction "2_2") (pintype "passive"))
      (node (ref "D25") (pin "1") (pinfunction "A_1") (pintype "passive"))
      (node (ref "M1") (pin "12") (pinfunction "VCC_12") (pintype "passive"))
      (node (ref "P10") (pin "1") (pinfunction "1_1") (pintype "passive"))
      (node (ref "P3") (pin "1") (pinfunction "1_1") (pintype "passive"))
      (node (ref "R17") (pin "2") (pinfunction "2_2") (pintype "passive"))
      (node (ref "R19") (pin "2") (pinfunction "2_2") (pintype "passive"))
      (node (ref "R21") (pin "2") (pinfunction "2_2") (pintype "passive"))
      (node (ref "R25") (pin "2") (pinfunction "2_2") (pintype "passive"))
      (node (ref "R58") (pin "2") (pinfunction "2_2") (pintype "passive"))
      (node (ref "U2") (pin "2") (pinfunction "VOUT_2") (pintype "passive"))
      (node (ref "U5") (pin "1") (pinfunction "VBAT_1") (pintype "power_in"))
      (node (ref "U5") (pin "19") (pinfunction "VDD_4_19") (pintype "power_in"))
      (node (ref "U5") (pin "32") (pinfunction "VDD_1_32") (pintype "power_in"))
      (node (ref "U5") (pin "48") (pinfunction "VDD_2_48") (pintype "power_in"))
      (node (ref "U5") (pin "64") (pinfunction "VDD_3_64") (pintype "power_in"))
      (node (ref "U7") (pin "8") (pinfunction "VCC_8") (pintype "passive"))
      (node (ref "U8") (pin "5") (pinfunction "Vio_5") (pintype "passive"))
    )
    (net (code "61") (name "5V") (class "Default")
      (node (ref "C36") (pin "2") (pinfunction "2_2") (pintype "passive"))
      (node (ref "C39") (pin "1") (pinfunction "1_1") (pintype "passive"))
      (node (ref "C6") (pin "1") (pinfunction "1_1") (pintype "passive"))
      (node (ref "C8") (pin "2") (pinfunction "2_2") (pintype "passive"))
      (node (ref "D3") (pin "2") (pinfunction "K_2") (pintype "passive"))
      (node (ref "I2") (pin "2") (pinfunction "2_2") (pintype "passive"))
      (node (ref "I3") (pin "2") (pinfunction "2_2") (pintype "passive"))
      (node (ref "R7") (pin "1") (pinfunction "1_1") (pintype "passive"))
      (node (ref "U2") (pin "3") (pinfunction "VIN_3") (pintype "passive"))
      (node (ref "U8") (pin "3") (pinfunction "VCC_3") (pintype "passive"))
    )
    (net (code "62") (name "24V") (class "Default")
      (node (ref "C29") (pin "2") (pinfunction "2_2") (pintype "passive"))
      (node (ref "C3") (pin "1") (pinfunction "1_1") (pintype "passive"))
      (node (ref "C30") (pin "2") (pinfunction "2_2") (pintype "passive"))
      (node (ref "D2") (pin "2") (pinfunction "K_2") (pintype "passive"))
      (node (ref "G2") (pin "1") (pinfunction "A_1") (pintype "passive"))
      (node (ref "G3") (pin "1") (pinfunction "A_1") (pintype "passive"))
      (node (ref "G4") (pin "1") (pinfunction "A_1") (pintype "passive"))
      (node (ref "G5") (pin "1") (pinfunction "A_1") (pintype "passive"))
      (node (ref "I1") (pin "2") (pinfunction "2_2") (pintype "passive"))
      (node (ref "I4") (pin "1") (pinfunction "1_1") (pintype "passive"))
      (node (ref "K1") (pin "1") (pinfunction "1_1") (pintype "passive"))
      (node (ref "K2") (pin "1") (pinfunction "1_1") (pintype "passive"))
      (node (ref "P5") (pin "1") (pinfunction "1_1") (pintype "passive"))
      (node (ref "R13") (pin "2") (pinfunction "2_2") (pintype "passive"))
      (node (ref "R4") (pin "1") (pinfunction "1_1") (pintype "passive"))
      (node (ref "U1") (pin "5") (pinfunction "VIN_5") (pintype "passive"))
      (node (ref "U6") (pin "5") (pinfunction "COM_5") (pintype "passive"))
    )
    (net (code "63") (name "A3.3V") (class "Default")
      (node (ref "C28") (pin "2") (pinfunction "2_2") (pintype "passive"))
      (node (ref "C34") (pin "2") (pinfunction "2_2") (pintype "passive"))
      (node (ref "U10") (pin "2") (pinfunction "VOUT_2") (pintype "passive"))
      (node (ref "U5") (pin "13") (pinfunction "VDDA_13") (pintype "power_in"))
    )
    (net (code "64") (name "A24V") (class "Default")
      (node (ref "C31") (pin "2") (pinfunction "2_2") (pintype "passive"))
      (node (ref "C32") (pin "1") (pinfunction "1_1") (pintype "passive"))
      (node (ref "I4") (pin "2") (pinfunction "2_2") (pintype "passive"))
      (node (ref "U9") (pin "4") (pinfunction "V+_4") (pintype "power_in"))
    )
    (net (code "65") (name "AGND") (class "Default")
      (node (ref "C23") (pin "1") (pinfunction "1_1") (pintype "passive"))
      (node (ref "C24") (pin "1") (pinfunction "1_1") (pintype "passive"))
      (node (ref "C25") (pin "1") (pinfunction "1_1") (pintype "passive"))
      (node (ref "C26") (pin "1") (pinfunction "1_1") (pintype "passive"))
      (node (ref "C28") (pin "1") (pinfunction "1_1") (pintype "passive"))
      (node (ref "C31") (pin "1") (pinfunction "1_1") (pintype "passive"))
      (node (ref "C32") (pin "2") (pinfunction "2_2") (pintype "passive"))
      (node (ref "C33") (pin "1") (pinfunction "1_1") (pintype "passive"))
      (node (ref "C34") (pin "1") (pinfunction "1_1") (pintype "passive"))
      (node (ref "C37") (pin "1") (pinfunction "1_1") (pintype "passive"))
      (node (ref "D15") (pin "1") (pinfunction "A_1") (pintype "passive"))
      (node (ref "D19") (pin "1") (pinfunction "A_1") (pintype "passive"))
      (node (ref "D21") (pin "1") (pinfunction "A_1") (pintype "passive"))
      (node (ref "D22") (pin "1") (pinfunction "A_1") (pintype "passive"))
      (node (ref "D23") (pin "1") (pinfunction "A_1") (pintype "passive"))
      (node (ref "D24") (pin "1") (pinfunction "A_1") (pintype "passive"))
      (node (ref "P6") (pin "2") (pinfunction "2_2") (pintype "passive"))
      (node (ref "P6") (pin "5") (pinfunction "5_5") (pintype "passive"))
      (node (ref "P6") (pin "8") (pinfunction "8_8") (pintype "passive"))
      (node (ref "Q1") (pin "2") (pinfunction "S_2") (pintype "passive"))
      (node (ref "Q2") (pin "2") (pinfunction "S_2") (pintype "passive"))
      (node (ref "Q3") (pin "2") (pinfunction "S_2") (pintype "passive"))
      (node (ref "Q4") (pin "2") (pinfunction "S_2") (pintype "passive"))
      (node (ref "R34") (pin "1") (pinfunction "1_1") (pintype "passive"))
      (node (ref "R39") (pin "1") (pinfunction "1_1") (pintype "passive"))
      (node (ref "R43") (pin "1") (pinfunction "1_1") (pintype "passive"))
      (node (ref "R47") (pin "1") (pinfunction "1_1") (pintype "passive"))
      (node (ref "R49") (pin "2") (pinfunction "2_2") (pintype "passive"))
      (node (ref "R51") (pin "2") (pinfunction "2_2") (pintype "passive"))
      (node (ref "R52") (pin "2") (pinfunction "2_2") (pintype "passive"))
      (node (ref "U10") (pin "1") (pinfunction "VSS_1") (pintype "passive"))
      (node (ref "U5") (pin "12") (pinfunction "VSSA_12") (pintype "power_in"))
      (node (ref "U9") (pin "11") (pinfunction "V-_11") (pintype "power_in"))
    )
    (net (code "66") (name "GND") (class "Default")
      (node (ref "C10") (pin "1") (pinfunction "1_1") (pintype "passive"))
      (node (ref "C11") (pin "1") (pinfunction "1_1") (pintype "passive"))
      (node (ref "C16") (pin "1") (pinfunction "1_1") (pintype "passive"))
      (node (ref "C17") (pin "1") (pinfunction "1_1") (pintype "passive"))
      (node (ref "C18") (pin "1") (pinfunction "1_1") (pintype "passive"))
      (node (ref "C19") (pin "1") (pinfunction "1_1") (pintype "passive"))
      (node (ref "C2") (pin "2") (pinfunction "2_2") (pintype "passive"))
      (node (ref "C20") (pin "1") (pinfunction "1_1") (pintype "passive"))
      (node (ref "C21") (pin "1") (pinfunction "1_1") (pintype "passive"))
      (node (ref "C22") (pin "1") (pinfunction "1_1") (pintype "passive"))
      (node (ref "C27") (pin "2") (pinfunction "2_2") (pintype "passive"))
      (node (ref "C29") (pin "1") (pinfunction "1_1") (pintype "passive"))
      (node (ref "C3") (pin "2") (pinfunction "2_2") (pintype "passive"))
      (node (ref "C30") (pin "1") (pinfunction "1_1") (pintype "passive"))
      (node (ref "C35") (pin "1") (pinfunction "1_1") (pintype "passive"))
      (node (ref "C36") (pin "1") (pinfunction "1_1") (pintype "passive"))
      (node (ref "C38") (pin "2") (pinfunction "2_2") (pintype "passive"))
      (node (ref "C39") (pin "2") (pinfunction "2_2") (pintype "passive"))
      (node (ref "C6") (pin "2") (pinfunction "2_2") (pintype "passive"))
      (node (ref "C8") (pin "1") (pinfunction "1_1") (pintype "passive"))
      (node (ref "C9") (pin "1") (pinfunction "1_1") (pintype "passive"))
      (node (ref "D10") (pin "1") (pinfunction "A_1") (pintype "passive"))
      (node (ref "D12") (pin "1") (pinfunction "A_1") (pintype "passive"))
      (node (ref "D14") (pin "1") (pinfunction "A_1") (pintype "passive"))
      (node (ref "D16") (pin "1") (pinfunction "A_1") (pintype "passive"))
      (node (ref "D17") (pin "1") (pinfunction "A_1") (pintype "passive"))
      (node (ref "D18") (pin "1") (pinfunction "A_1") (pintype "passive"))
      (node (ref "D2") (pin "1") (pinfunction "A_1") (pintype "passive"))
      (node (ref "D20") (pin "1") (pinfunction "A_1") (pintype "passive"))
      (node (ref "D3") (pin "1") (pinfunction "A_1") (pintype "passive"))
      (node (ref "D8") (pin "1") (pinfunction "A_1") (pintype "passive"))
      (node (ref "G2") (pin "3") (pinfunction "E_3") (pintype "passive"))
      (node (ref "G3") (pin "3") (pinfunction "E_3") (pintype "passive"))
      (node (ref "G4") (pin "3") (pinfunction "E_3") (pintype "passive"))
      (node (ref "G5") (pin "3") (pinfunction "E_3") (pintype "passive"))
      (node (ref "M1") (pin "1") (pinfunction "GND_1") (pintype "passive"))
      (node (ref "P10") (pin "11") (pinfunction "11_11") (pintype "passive"))
      (node (ref "P10") (pin "12") (pinfunction "12_12") (pintype "passive"))
      (node (ref "P10") (pin "2") (pinfunction "2_2") (pintype "passive"))
      (node (ref "P2") (pin "2") (pinfunction "2_2") (pintype "passive"))
      (node (ref "P2") (pin "5") (pinfunction "5_5") (pintype "passive"))
      (node (ref "P3") (pin "3") (pinfunction "3_3") (pintype "passive"))
      (node (ref "P5") (pin "2") (pinfunction "2_2") (pintype "passive"))
      (node (ref "R16") (pin "1") (pinfunction "1_1") (pintype "passive"))
      (node (ref "R23") (pin "2") (pinfunction "2_2") (pintype "passive"))
      (node (ref "R24") (pin "2") (pinfunction "2_2") (pintype "passive"))
      (node (ref "R35") (pin "1") (pinfunction "1_1") (pintype "passive"))
      (node (ref "R52") (pin "1") (pinfunction "1_1") (pintype "passive"))
      (node (ref "R9") (pin "2") (pinfunction "2_2") (pintype "passive"))
      (node (ref "T1") (pin "6") (pinfunction "6_6") (pintype "passive"))
      (node (ref "T1") (pin "7") (pinfunction "7_7") (pintype "passive"))
      (node (ref "U1") (pin "2") (pinfunction "GND_2") (pintype "passive"))
      (node (ref "U2") (pin "1") (pinfunction "VSS_1") (pintype "passive"))
      (node (ref "U4") (pin "3") (pinfunction "A_3") (pintype "passive"))
      (node (ref "U5") (pin "18") (pinfunction "VSS_4_18") (pintype "power_in"))
      (node (ref "U5") (pin "31") (pinfunction "VSS_1_31") (pintype "power_in"))
      (node (ref "U5") (pin "47") (pinfunction "VSS_2_47") (pintype "power_in"))
      (node (ref "U5") (pin "63") (pinfunction "VSS_3_63") (pintype "power_in"))
      (node (ref "U6") (pin "4") (pinfunction "E_4") (pintype "passive"))
      (node (ref "U7") (pin "5") (pinfunction "GND_5") (pintype "passive"))
      (node (ref "U8") (pin "2") (pinfunction "GND_2") (pintype "passive"))
      (node (ref "U8") (pin "8") (pinfunction "S_8") (pintype "passive"))
    )
    (net (code "67") (name "Net-(C4-Pad1)") (class "Default")
      (node (ref "C4") (pin "1") (pinfunction "1_1") (pintype "passive"))
      (node (ref "L1") (pin "4") (pinfunction "4_4") (pintype "passive"))
      (node (ref "R1") (pin "2") (pinfunction "2_2") (pintype "passive"))
      (node (ref "R5") (pin "2") (pinfunction "2_2") (pintype "passive"))
    )
    (net (code "68") (name "Net-(C5-Pad1)") (class "Default")
      (node (ref "C5") (pin "1") (pinfunction "1_1") (pintype "passive"))
      (node (ref "D5") (pin "2") (pinfunction "C_2") (pintype "passive"))
      (node (ref "L1") (pin "3") (pinfunction "3_3") (pintype "passive"))
    )
    (net (code "69") (name "Net-(C5-Pad2)") (class "Default")
      (node (ref "C5") (pin "2") (pinfunction "2_2") (pintype "passive"))
      (node (ref "D5") (pin "1") (pinfunction "C_1") (pintype "passive"))
      (node (ref "L1") (pin "2") (pinfunction "2_2") (pintype "passive"))
    )
    (net (code "70") (name "Net-(C7-Pad1)") (class "Default")
      (node (ref "C7") (pin "1") (pinfunction "1_1") (pintype "passive"))
      (node (ref "R2") (pin "1") (pinfunction "1_1") (pintype "passive"))
    )
    (net (code "71") (name "Net-(D1-A)") (class "Default")
      (node (ref "D1") (pin "1") (pinfunction "A_1") (pintype "passive"))
      (node (ref "T1") (pin "5") (pinfunction "5_5") (pintype "passive"))
      (node (ref "T1") (pin "8") (pinfunction "8_8") (pintype "passive"))
    )
    (net (code "72") (name "Net-(D1-K)") (class "Default")
      (node (ref "C2") (pin "1") (pinfunction "1_1") (pintype "passive"))
      (node (ref "D1") (pin "2") (pinfunction "K_2") (pintype "passive"))
      (node (ref "I1") (pin "1") (pinfunction "1_1") (pintype "passive"))
      (node (ref "R12") (pin "2") (pinfunction "2_2") (pintype "passive"))
    )
    (net (code "73") (name "Net-(D4-A)") (class "Default")
      (node (ref "D4") (pin "1") (pinfunction "A_1") (pintype "passive"))
      (node (ref "T1") (pin "2") (pinfunction "2_2") (pintype "passive"))
      (node (ref "U3") (pin "5") (pinfunction "Drain_5") (pintype "passive"))
      (node (ref "U3") (pin "6") (pinfunction "Drain_6") (pintype "passive"))
    )
    (net (code "74") (name "Net-(D4-K)") (class "Default")
      (node (ref "D4") (pin "2") (pinfunction "K_2") (pintype "passive"))
      (node (ref "R2") (pin "2") (pinfunction "2_2") (pintype "passive"))
      (node (ref "R3") (pin "1") (pinfunction "1_1") (pintype "passive"))
    )
    (net (code "75") (name "Net-(D5-K)") (class "Default")
      (node (ref "C12") (pin "1") (pinfunction "1_1") (pintype "passive"))
      (node (ref "C7") (pin "2") (pinfunction "2_2") (pintype "passive"))
      (node (ref "D5") (pin "3") (pinfunction "K_3") (pintype "passive"))
      (node (ref "R3") (pin "2") (pinfunction "2_2") (pintype "passive"))
      (node (ref "R6") (pin "1") (pinfunction "1_1") (pintype "passive"))
      (node (ref "T1") (pin "1") (pinfunction "1_1") (pintype "passive"))
    )
    (net (code "76") (name "Net-(D6-A)") (class "Default")
      (node (ref "D6") (pin "1") (pinfunction "A_1") (pintype "passive"))
      (node (ref "T1") (pin "4") (pinfunction "4_4") (pintype "passive"))
    )
    (net (code "77") (name "Net-(D6-K)") (class "Default")
      (node (ref "C13") (pin "2") (pinfunction "2_2") (pintype "passive"))
      (node (ref "D6") (pin "2") (pinfunction "K_2") (pintype "passive"))
      (node (ref "R10") (pin "2") (pinfunction "2_2") (pintype "passive"))
      (node (ref "R11") (pin "2") (pinfunction "2_2") (pintype "passive"))
      (node (ref "R8") (pin "2") (pinfunction "2_2") (pintype "passive"))
    )
    (net (code "78") (name "Net-(D25-K)") (class "Default")
      (node (ref "D25") (pin "2") (pinfunction "K_2") (pintype "passive"))
      (node (ref "R27") (pin "1") (pinfunction "1_1") (pintype "passive"))
    )
    (net (code "79") (name "Net-(F1-Pad2)") (class "Default")
      (node (ref "F1") (pin "2") (pinfunction "2_2") (pintype "passive"))
      (node (ref "R1") (pin "1") (pinfunction "1_1") (pintype "passive"))
    )
    (net (code "80") (name "Net-(G1-A)") (class "Default")
      (node (ref "G1") (pin "1") (pinfunction "A_1") (pintype "passive"))
      (node (ref "R12") (pin "1") (pinfunction "1_1") (pintype "passive"))
    )
    (net (code "81") (name "Net-(G1-C)") (class "Default")
      (node (ref "C15") (pin "2") (pinfunction "2_2") (pintype "passive"))
      (node (ref "G1") (pin "4") (pinfunction "C_4") (pintype "passive"))
      (node (ref "U3") (pin "1") (pinfunction "FB_1") (pintype "passive"))
    )
    (net (code "82") (name "Net-(G1-K)") (class "Default")
      (node (ref "C14") (pin "1") (pinfunction "1_1") (pintype "passive"))
      (node (ref "G1") (pin "2") (pinfunction "K_2") (pintype "passive"))
      (node (ref "U4") (pin "2") (pinfunction "K_2") (pintype "passive"))
    )
    (net (code "83") (name "Net-(G2-K)") (class "Default")
      (node (ref "C16") (pin "2") (pinfunction "2_2") (pintype "passive"))
      (node (ref "G2") (pin "2") (pinfunction "K_2") (pintype "passive"))
      (node (ref "R18") (pin "2") (pinfunction "2_2") (pintype "passive"))
    )
    (net (code "84") (name "Net-(G3-K)") (class "Default")
      (node (ref "C17") (pin "2") (pinfunction "2_2") (pintype "passive"))
      (node (ref "G3") (pin "2") (pinfunction "K_2") (pintype "passive"))
      (node (ref "R20") (pin "2") (pinfunction "2_2") (pintype "passive"))
    )
    (net (code "85") (name "Net-(G4-K)") (class "Default")
      (node (ref "C19") (pin "2") (pinfunction "2_2") (pintype "passive"))
      (node (ref "G4") (pin "2") (pinfunction "K_2") (pintype "passive"))
      (node (ref "R22") (pin "2") (pinfunction "2_2") (pintype "passive"))
    )
    (net (code "86") (name "Net-(G5-K)") (class "Default")
      (node (ref "C22") (pin "2") (pinfunction "2_2") (pintype "passive"))
      (node (ref "G5") (pin "2") (pinfunction "K_2") (pintype "passive"))
      (node (ref "R26") (pin "2") (pinfunction "2_2") (pintype "passive"))
    )
    (net (code "87") (name "Net-(P4-Pad1)") (class "Default")
      (node (ref "P4") (pin "1") (pinfunction "1_1") (pintype "passive"))
      (node (ref "R32") (pin "2") (pinfunction "2_2") (pintype "passive"))
    )
    (net (code "88") (name "Net-(P9-Pad2)") (class "Default")
      (node (ref "P9") (pin "2") (pinfunction "2_2") (pintype "passive"))
      (node (ref "R53") (pin "1") (pinfunction "1_1") (pintype "passive"))
    )
    (net (code "89") (name "Net-(Q1-D)") (class "Default")
      (node (ref "Q1") (pin "3") (pinfunction "D_3") (pintype "passive"))
      (node (ref "R29") (pin "1") (pinfunction "1_1") (pintype "passive"))
      (node (ref "R30") (pin "1") (pinfunction "1_1") (pintype "passive"))
    )
    (net (code "90") (name "Net-(Q2-D)") (class "Default")
      (node (ref "Q2") (pin "3") (pinfunction "D_3") (pintype "passive"))
      (node (ref "R36") (pin "1") (pinfunction "1_1") (pintype "passive"))
      (node (ref "R37") (pin "1") (pinfunction "1_1") (pintype "passive"))
    )
    (net (code "91") (name "Net-(Q3-D)") (class "Default")
      (node (ref "Q3") (pin "3") (pinfunction "D_3") (pintype "passive"))
      (node (ref "R40") (pin "1") (pinfunction "1_1") (pintype "passive"))
      (node (ref "R41") (pin "1") (pinfunction "1_1") (pintype "passive"))
    )
    (net (code "92") (name "Net-(Q4-D)") (class "Default")
      (node (ref "Q4") (pin "3") (pinfunction "D_3") (pintype "passive"))
      (node (ref "R44") (pin "1") (pinfunction "1_1") (pintype "passive"))
      (node (ref "R45") (pin "1") (pinfunction "1_1") (pintype "passive"))
    )
    (net (code "93") (name "Net-(R6-Pad2)") (class "Default")
      (node (ref "R6") (pin "2") (pinfunction "2_2") (pintype "passive"))
      (node (ref "R8") (pin "1") (pinfunction "1_1") (pintype "passive"))
    )
    (net (code "94") (name "Net-(U1-BST)") (class "Default")
      (node (ref "C1") (pin "2") (pinfunction "2_2") (pintype "passive"))
      (node (ref "U1") (pin "1") (pinfunction "BST_1") (pintype "passive"))
    )
    (net (code "95") (name "Net-(U1-EN)") (class "Default")
      (node (ref "R4") (pin "2") (pinfunction "2_2") (pintype "passive"))
      (node (ref "U1") (pin "4") (pinfunction "EN_4") (pintype "passive"))
    )
    (net (code "96") (name "Net-(U1-FB)") (class "Default")
      (node (ref "R7") (pin "2") (pinfunction "2_2") (pintype "passive"))
      (node (ref "R9") (pin "1") (pinfunction "1_1") (pintype "passive"))
      (node (ref "U1") (pin "3") (pinfunction "FB_3") (pintype "passive"))
    )
    (net (code "97") (name "Net-(U1-SW)") (class "Default")
      (node (ref "C1") (pin "1") (pinfunction "1_1") (pintype "passive"))
      (node (ref "I2") (pin "1") (pinfunction "1_1") (pintype "passive"))
      (node (ref "U1") (pin "6") (pinfunction "SW_6") (pintype "passive"))
    )
    (net (code "98") (name "Net-(U3-Sense)") (class "Default")
      (node (ref "R14") (pin "2") (pinfunction "2_2") (pintype "passive"))
      (node (ref "R15") (pin "2") (pinfunction "2_2") (pintype "passive"))
      (node (ref "U3") (pin "4") (pinfunction "Sense_4") (pintype "passive"))
    )
    (net (code "99") (name "Net-(U3-VDD)") (class "Default")
      (node (ref "R11") (pin "1") (pinfunction "1_1") (pintype "passive"))
      (node (ref "U3") (pin "3") (pinfunction "VDD_3") (pintype "passive"))
    )
    (net (code "100") (name "Net-(U3-VDD_G)") (class "Default")
      (node (ref "R10") (pin "1") (pinfunction "1_1") (pintype "passive"))
      (node (ref "U3") (pin "2") (pinfunction "VDD_G_2") (pintype "passive"))
    )
    (net (code "101") (name "Net-(U4-REF)") (class "Default")
      (node (ref "C14") (pin "2") (pinfunction "2_2") (pintype "passive"))
      (node (ref "R13") (pin "1") (pinfunction "1_1") (pintype "passive"))
      (node (ref "R16") (pin "2") (pinfunction "2_2") (pintype "passive"))
      (node (ref "U4") (pin "1") (pinfunction "REF_1") (pintype "passive"))
    )
    (net (code "102") (name "Net-(U5-BOOT0)") (class "Default")
      (node (ref "R23") (pin "1") (pinfunction "1_1") (pintype "passive"))
      (node (ref "U5") (pin "60") (pinfunction "BOOT0_60") (pintype "input"))
    )
    (net (code "103") (name "Net-(U5-PB2)") (class "Default")
      (node (ref "R24") (pin "1") (pinfunction "1_1") (pintype "passive"))
      (node (ref "U5") (pin "28") (pinfunction "PB2_28") (pintype "bidirectional"))
    )
    (net (code "104") (name "Net-(U5-PD0-OSC_IN)") (class "Default")
      (node (ref "C20") (pin "2") (pinfunction "2_2") (pintype "passive"))
      (node (ref "U5") (pin "5") (pinfunction "PD0-OSC_IN_5") (pintype "bidirectional"))
      (node (ref "Y1") (pin "2") (pinfunction "OSC2_2") (pintype "passive"))
    )
    (net (code "105") (name "Net-(U5-PD1)") (class "Default")
      (node (ref "C21") (pin "2") (pinfunction "2_2") (pintype "passive"))
      (node (ref "U5") (pin "6") (pinfunction "PD1_6") (pintype "bidirectional"))
      (node (ref "Y1") (pin "1") (pinfunction "OSC1_1") (pintype "passive"))
    )
    (net (code "106") (name "Net-(U6-2C)") (class "Default")
      (node (ref "K1") (pin "2") (pinfunction "2_2") (pintype "passive"))
      (node (ref "U6") (pin "7") (pinfunction "2C_7") (pintype "passive"))
    )
    (net (code "107") (name "Net-(U6-3C)") (class "Default")
      (node (ref "K2") (pin "2") (pinfunction "2_2") (pintype "passive"))
      (node (ref "U6") (pin "6") (pinfunction "3C_6") (pintype "passive"))
    )
    (net (code "108") (name "Net-(U7-A)") (class "Default")
      (node (ref "R28") (pin "2") (pinfunction "2_2") (pintype "passive"))
      (node (ref "U7") (pin "6") (pinfunction "A_6") (pintype "passive"))
    )
    (net (code "109") (name "Net-(U7-B)") (class "Default")
      (node (ref "R33") (pin "2") (pinfunction "2_2") (pintype "passive"))
      (node (ref "U7") (pin "7") (pinfunction "B_7") (pintype "passive"))
    )
    (net (code "110") (name "Net-(U9A-IN+)") (class "Default")
      (node (ref "R55") (pin "1") (pinfunction "1_1") (pintype "passive"))
      (node (ref "U9") (pin "3") (pinfunction "IN+_3") (pintype "input"))
    )
    (net (code "111") (name "Net-(U9A-IN-)") (class "Default")
      (node (ref "R50") (pin "1") (pinfunction "1_1") (pintype "passive"))
      (node (ref "R51") (pin "1") (pinfunction "1_1") (pintype "passive"))
      (node (ref "U9") (pin "2") (pinfunction "IN-_2") (pintype "input"))
    )
    (net (code "112") (name "Net-(U9A-OUT)") (class "Default")
      (node (ref "R50") (pin "2") (pinfunction "2_2") (pintype "passive"))
      (node (ref "U9") (pin "1") (pinfunction "OUT_1") (pintype "output"))
      (node (ref "U9") (pin "5") (pinfunction "IN+_5") (pintype "input"))
    )
    (net (code "113") (name "Net-(U9C-IN+)") (class "Default")
      (node (ref "R48") (pin "2") (pinfunction "2_2") (pintype "passive"))
      (node (ref "U9") (pin "10") (pinfunction "IN+_10") (pintype "input"))
      (node (ref "U9") (pin "14") (pinfunction "OUT_14") (pintype "output"))
    )
    (net (code "114") (name "Net-(U9D-IN+)") (class "Default")
      (node (ref "R54") (pin "1") (pinfunction "1_1") (pintype "passive"))
      (node (ref "U9") (pin "12") (pinfunction "IN+_12") (pintype "input"))
    )
    (net (code "115") (name "Net-(U9D-IN-)") (class "Default")
      (node (ref "R48") (pin "1") (pinfunction "1_1") (pintype "passive"))
      (node (ref "R49") (pin "1") (pinfunction "1_1") (pintype "passive"))
      (node (ref "U9") (pin "13") (pinfunction "IN-_13") (pintype "input"))
    )
    (net (code "116") (name "Net-(U10-VIN)") (class "Default")
      (node (ref "C33") (pin "2") (pinfunction "2_2") (pintype "passive"))
      (node (ref "C37") (pin "2") (pinfunction "2_2") (pintype "passive"))
      (node (ref "I3") (pin "1") (pinfunction "1_1") (pintype "passive"))
      (node (ref "U10") (pin "3") (pinfunction "VIN_3") (pintype "passive"))
    )
    (net (code "117") (name "unconnected-(M1-GPIO0-Pad11)") (class "Default")
      (node (ref "M1") (pin "11") (pinfunction "GPIO0_11") (pintype "passive+no_connect"))
    )
    (net (code "118") (name "unconnected-(M1-GPIO1-Pad10)") (class "Default")
      (node (ref "M1") (pin "10") (pinfunction "GPIO1_10") (pintype "passive+no_connect"))
    )
    (net (code "119") (name "unconnected-(M1-GPIO2-Pad4)") (class "Default")
      (node (ref "M1") (pin "4") (pinfunction "GPIO2_4") (pintype "passive+no_connect"))
    )
    (net (code "120") (name "unconnected-(M1-GPIO3-Pad3)") (class "Default")
      (node (ref "M1") (pin "3") (pinfunction "GPIO3_3") (pintype "passive+no_connect"))
    )
    (net (code "121") (name "unconnected-(U5-PA15-Pad50)") (class "Default")
      (node (ref "U5") (pin "50") (pinfunction "PA15_50") (pintype "bidirectional+no_connect"))
    )
    (net (code "122") (name "unconnected-(U5-PB8-Pad61)") (class "Default")
      (node (ref "U5") (pin "61") (pinfunction "PB8_61") (pintype "bidirectional+no_connect"))
    )
    (net (code "123") (name "unconnected-(U5-PB9-Pad62)") (class "Default")
      (node (ref "U5") (pin "62") (pinfunction "PB9_62") (pintype "bidirectional+no_connect"))
    )
    (net (code "124") (name "unconnected-(U5-PC0-Pad8)") (class "Default")
      (node (ref "U5") (pin "8") (pinfunction "PC0_8") (pintype "bidirectional+no_connect"))
    )
    (net (code "125") (name "unconnected-(U5-PC1-Pad9)") (class "Default")
      (node (ref "U5") (pin "9") (pinfunction "PC1_9") (pintype "bidirectional+no_connect"))
    )
    (net (code "126") (name "unconnected-(U5-PC2-Pad10)") (class "Default")
      (node (ref "U5") (pin "10") (pinfunction "PC2_10") (pintype "bidirectional+no_connect"))
    )
    (net (code "127") (name "unconnected-(U5-PC3-Pad11)") (class "Default")
      (node (ref "U5") (pin "11") (pinfunction "PC3_11") (pintype "bidirectional+no_connect"))
    )
    (net (code "128") (name "unconnected-(U5-PC8-Pad39)") (class "Default")
      (node (ref "U5") (pin "39") (pinfunction "PC8_39") (pintype "bidirectional+no_connect"))
    )
    (net (code "129") (name "unconnected-(U5-PC9-Pad40)") (class "Default")
      (node (ref "U5") (pin "40") (pinfunction "PC9_40") (pintype "bidirectional+no_connect"))
    )
    (net (code "130") (name "unconnected-(U5-PC10-Pad51)") (class "Default")
      (node (ref "U5") (pin "51") (pinfunction "PC10_51") (pintype "bidirectional+no_connect"))
    )
    (net (code "131") (name "unconnected-(U5-PC13-TAMPER-RTC-Pad2)") (class "Default")
      (node (ref "U5") (pin "2") (pinfunction "PC13-TAMPER-RTC_2") (pintype "bidirectional+no_connect"))
    )
    (net (code "132") (name "unconnected-(U6-1B-Pad1)") (class "Default")
      (node (ref "U6") (pin "1") (pinfunction "1B_1") (pintype "passive+no_connect"))
    )
    (net (code "133") (name "unconnected-(U6-1C-Pad8)") (class "Default")
      (node (ref "U6") (pin "8") (pinfunction "1C_8") (pintype "passive+no_connect"))
    )
  )
)
